# cabletester.net
KiCad netlist of a schematic drawn in EAGLE
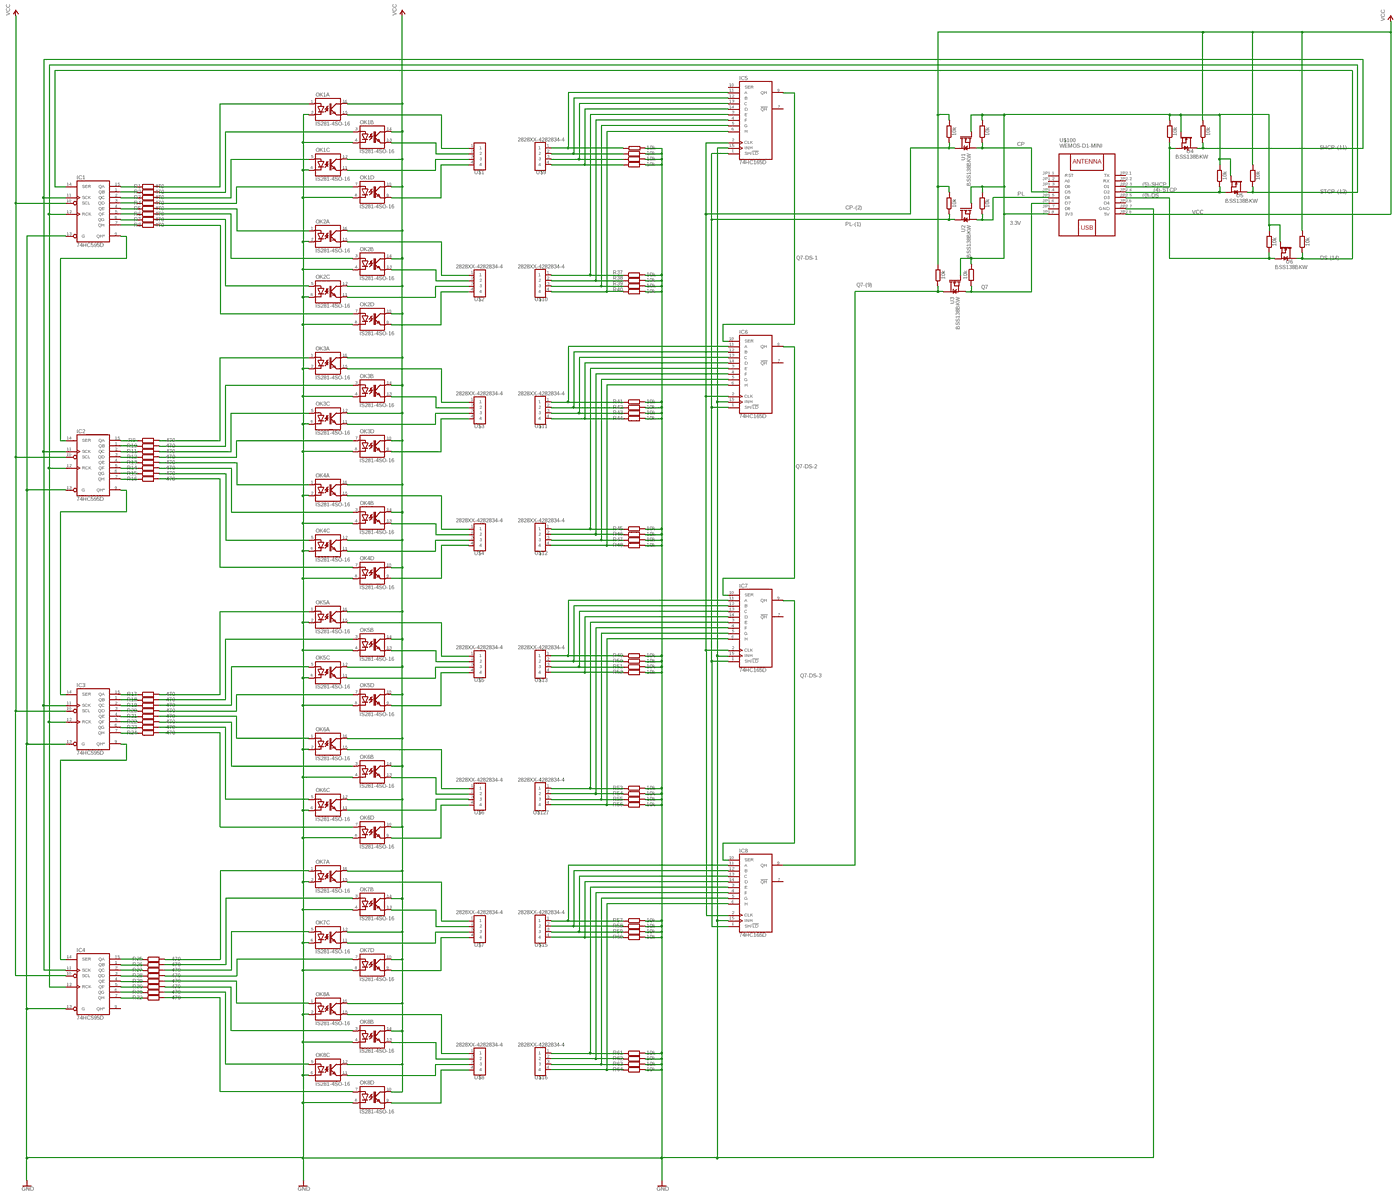
[diagram p0: schematic, sheet 1, overview]
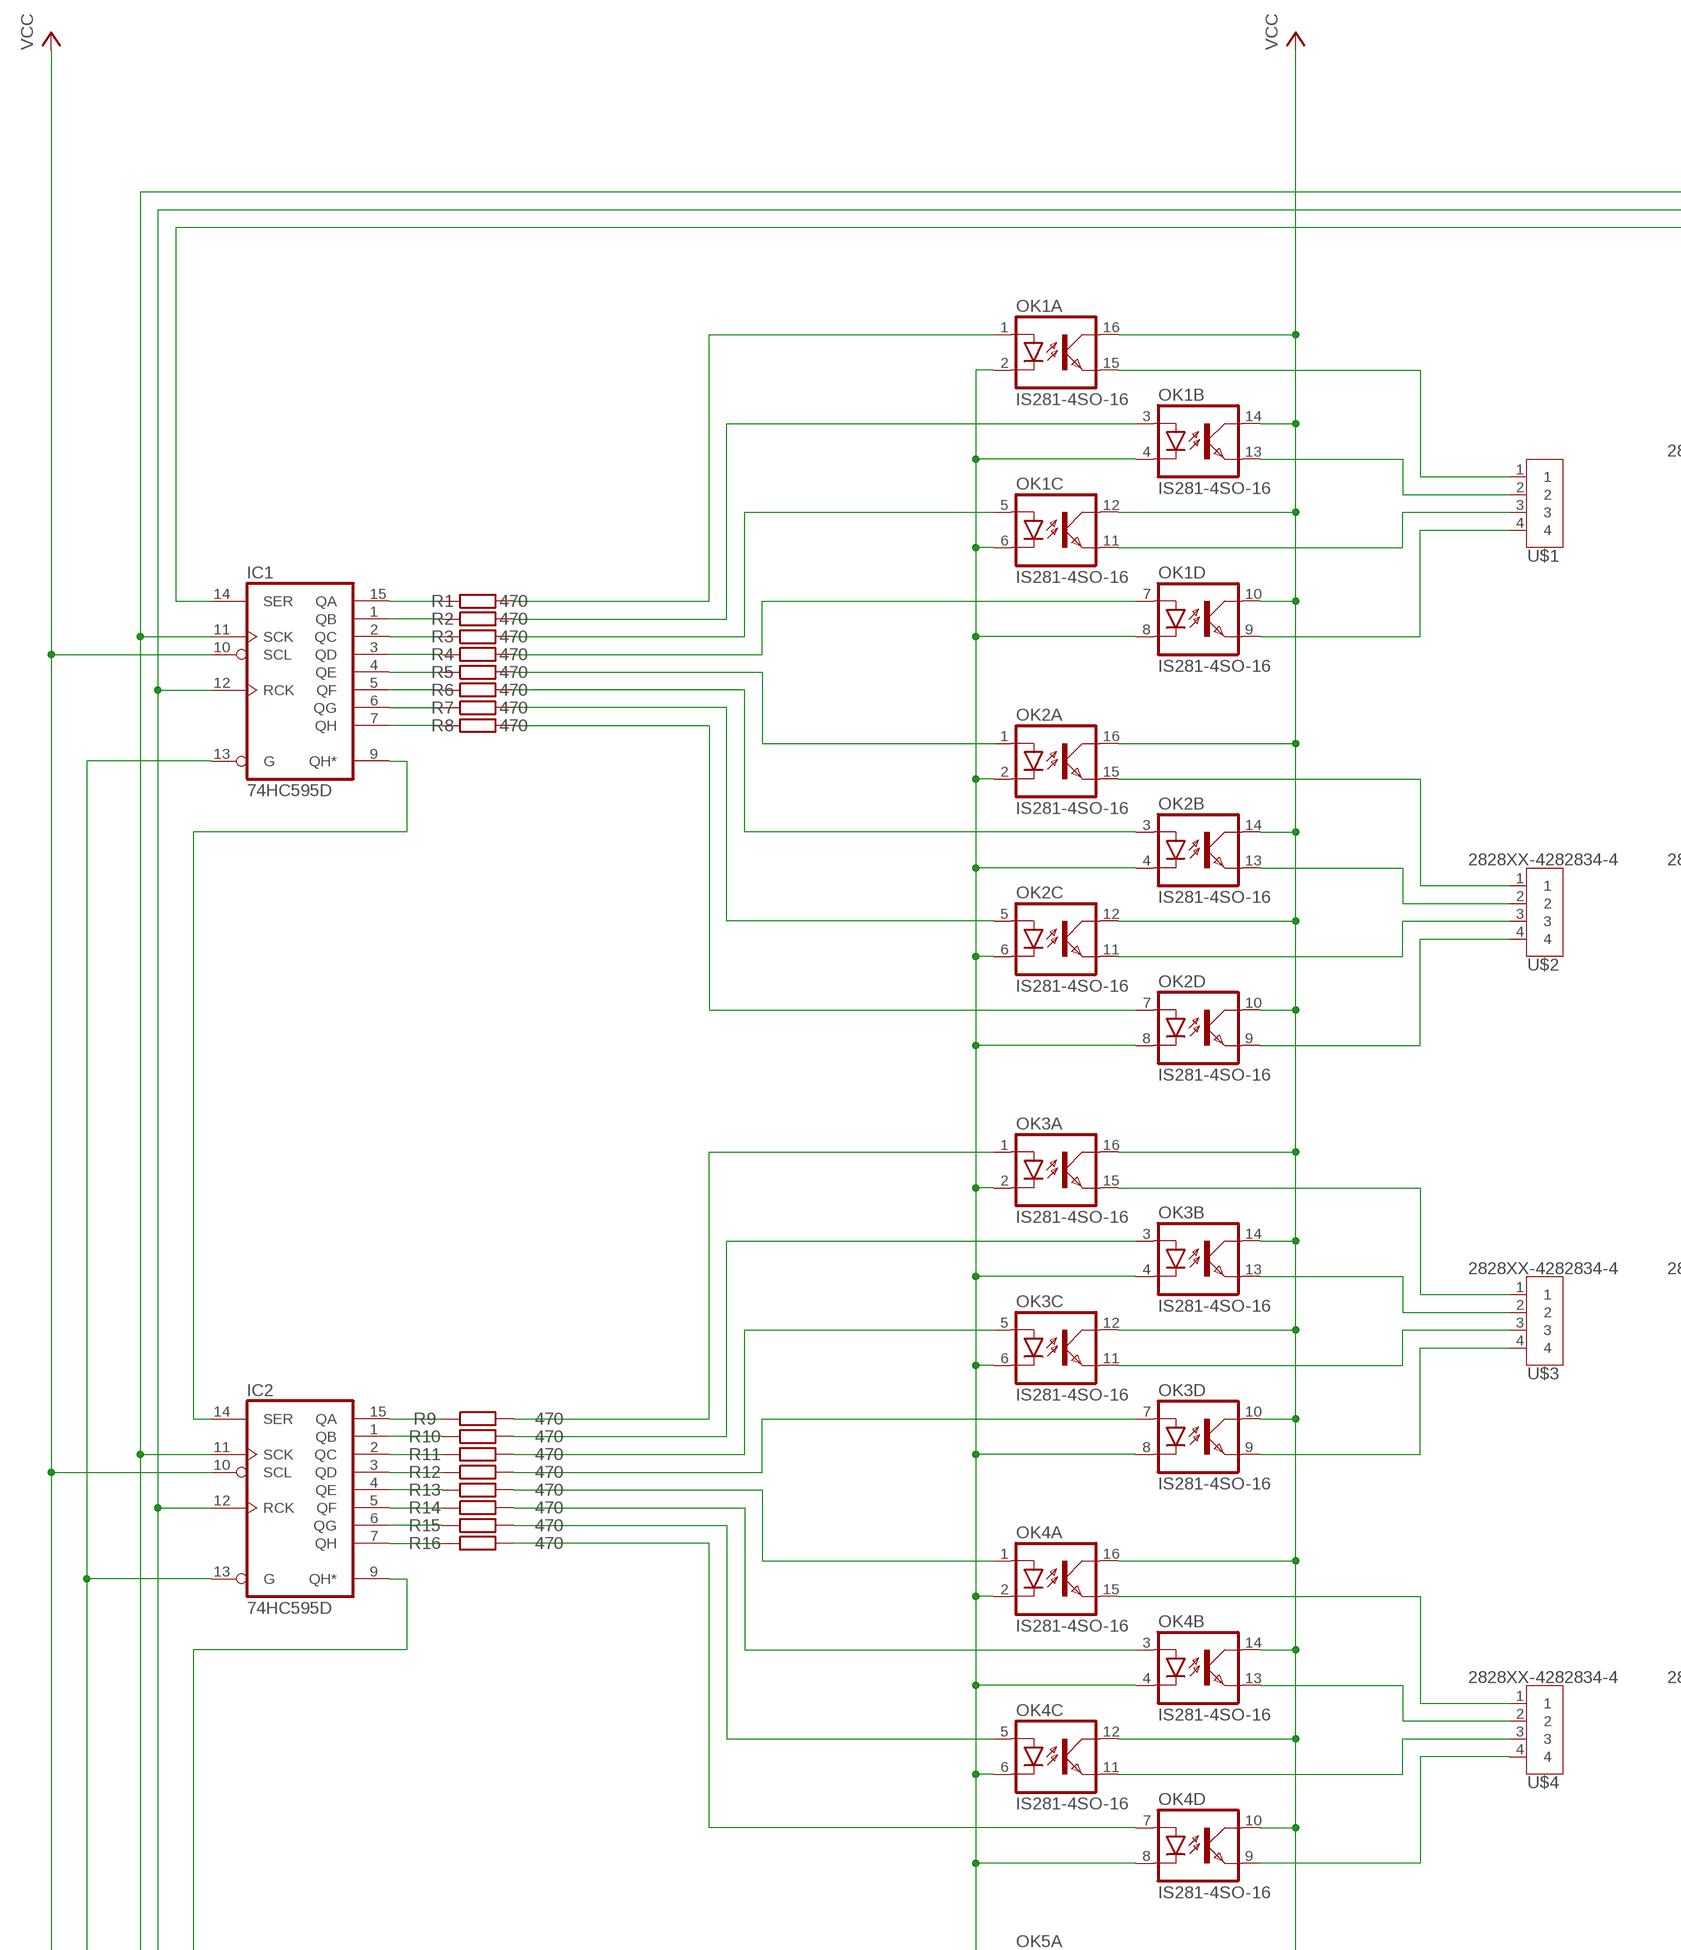
[diagram p1: schematic, sheet 1, part 1 of 4]
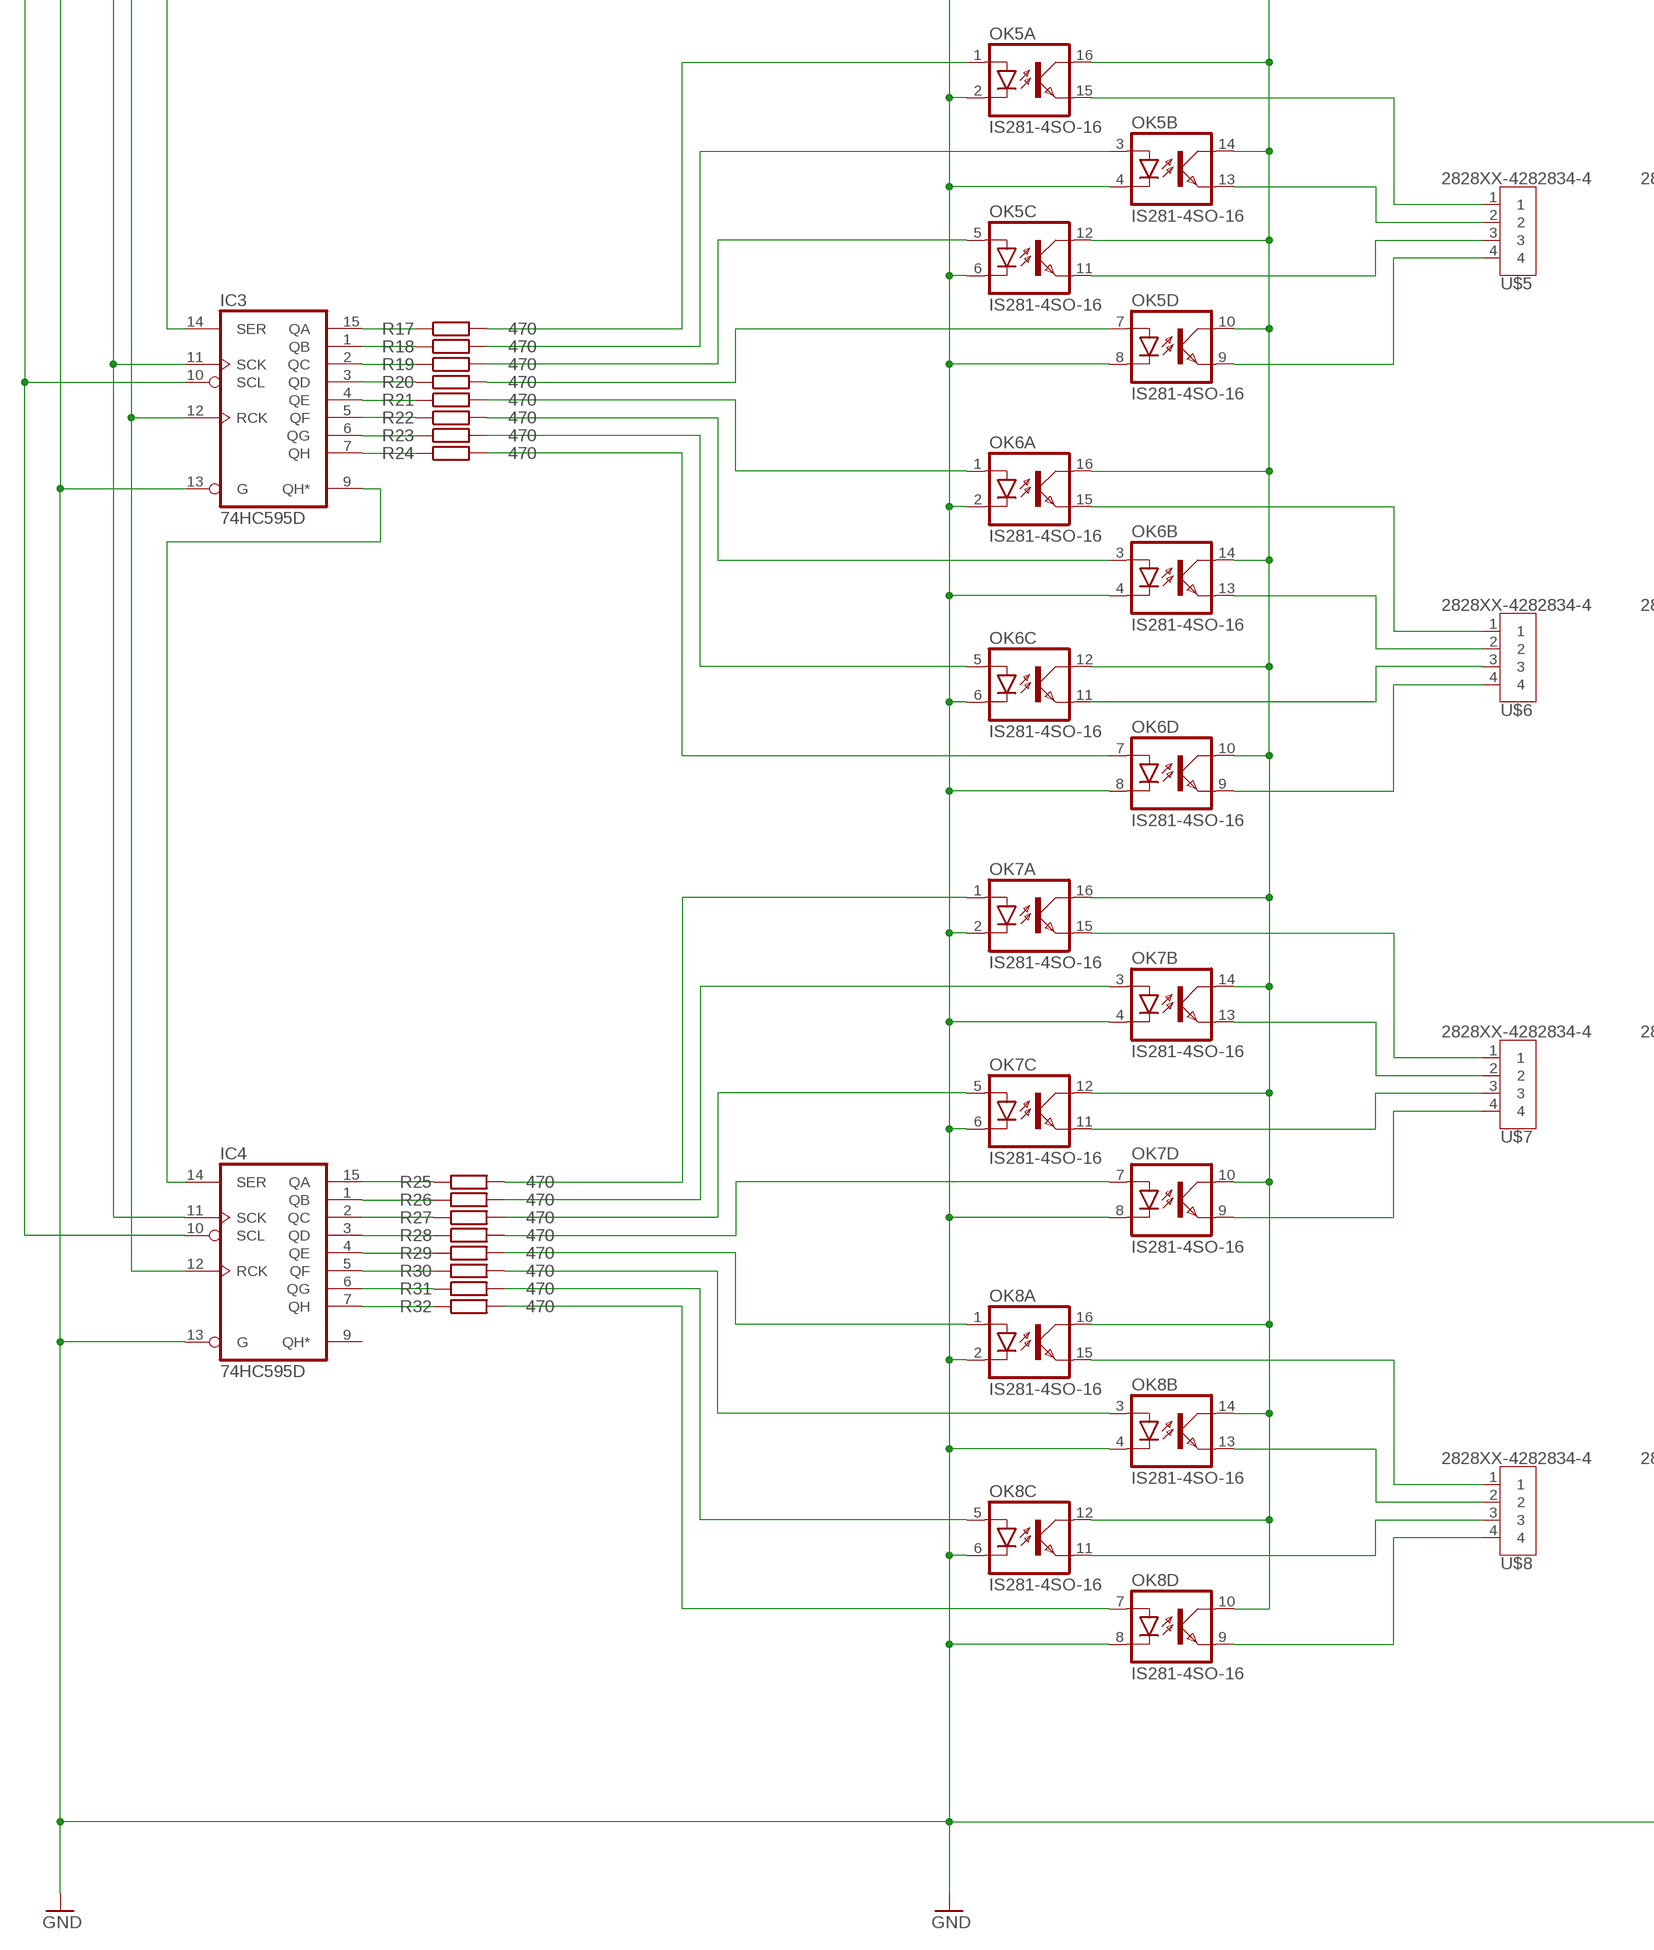
[diagram p2: schematic, sheet 1, part 2 of 4]
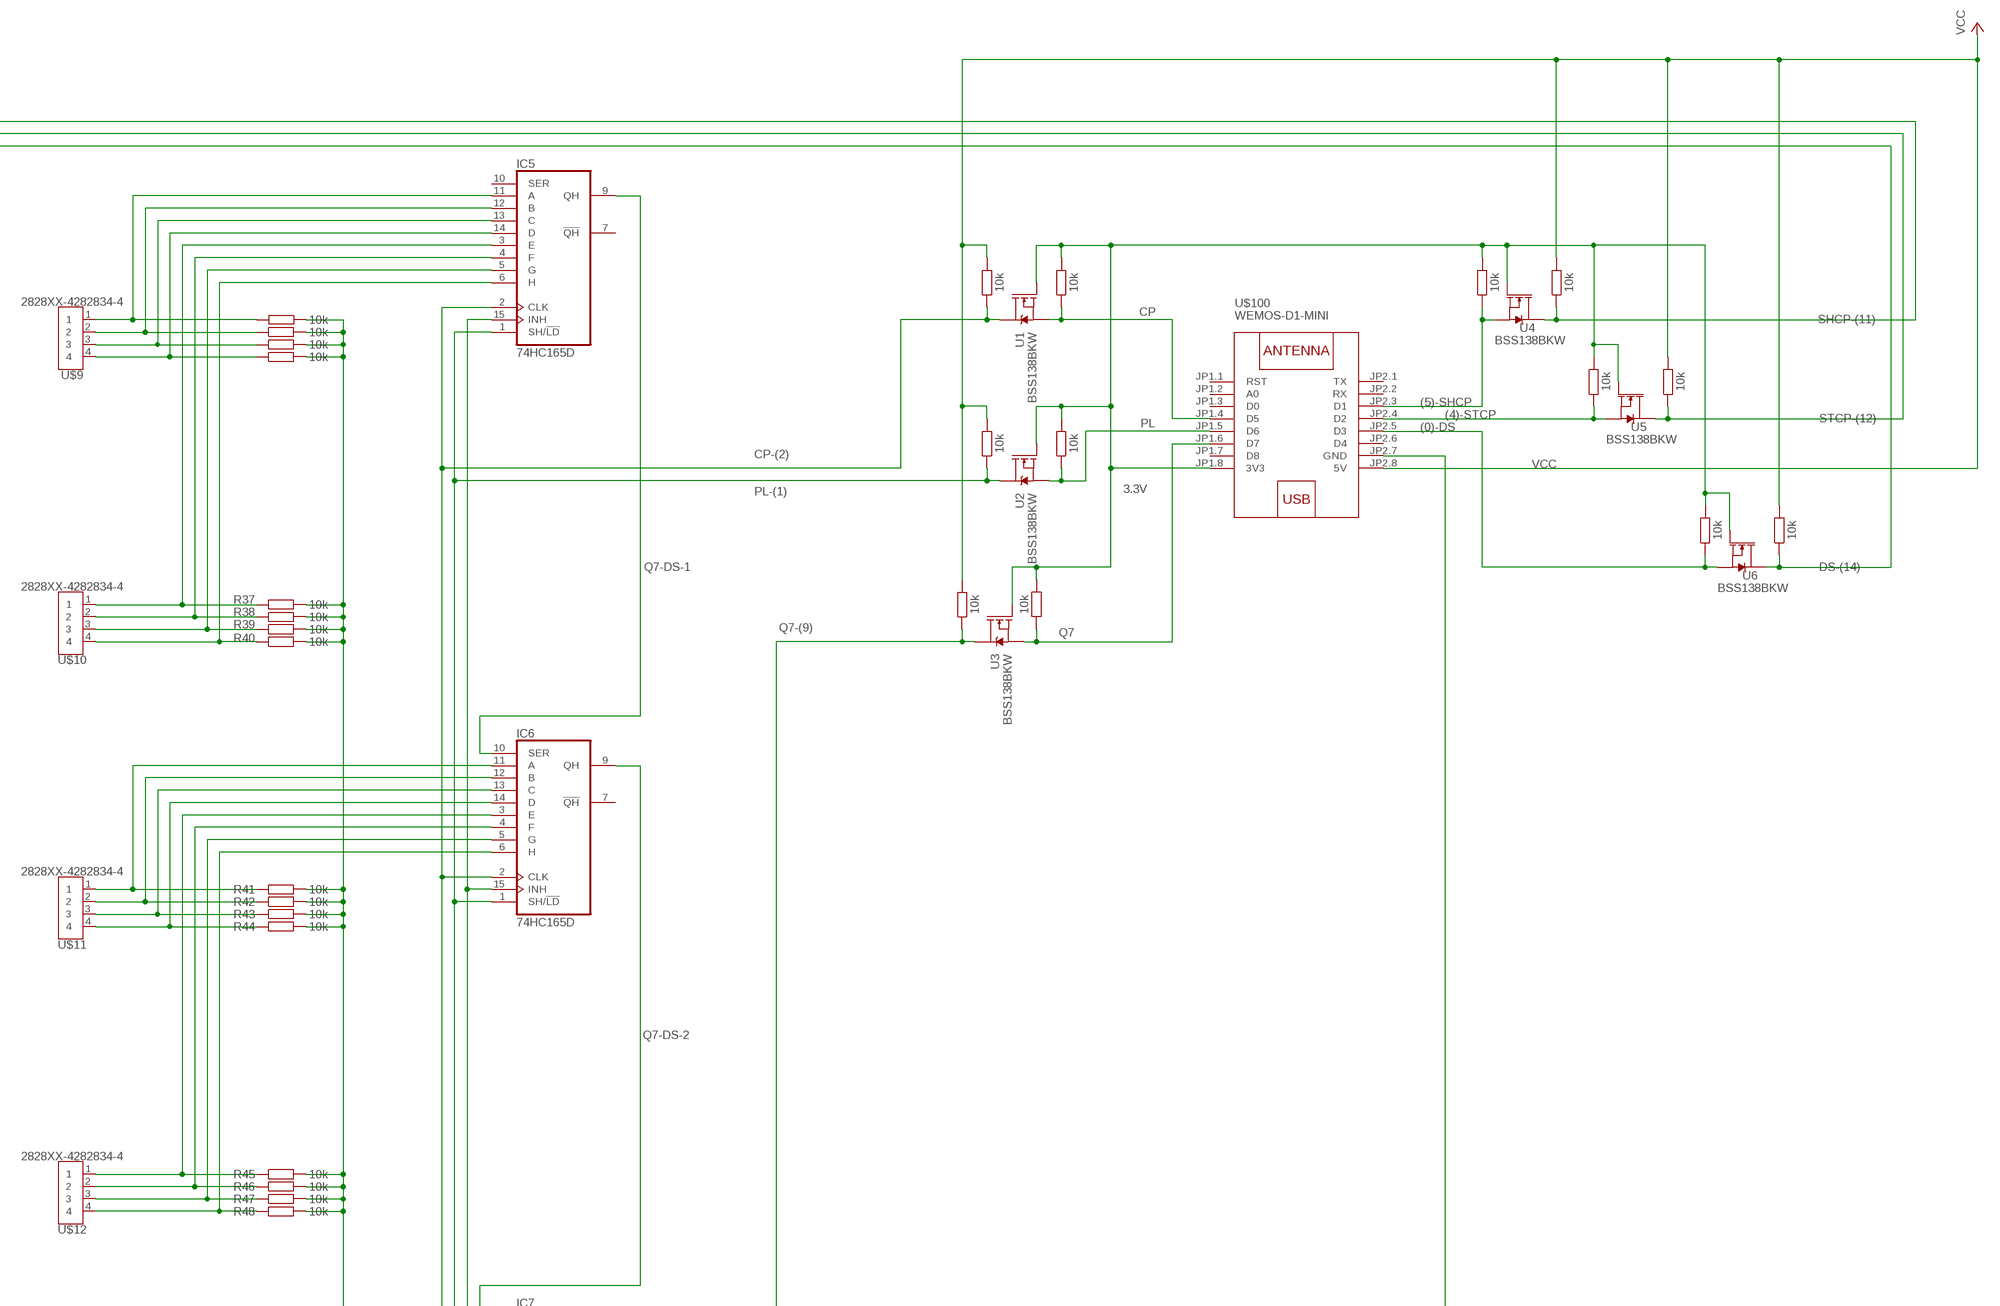
[diagram p3: schematic, sheet 1, part 3 of 4]
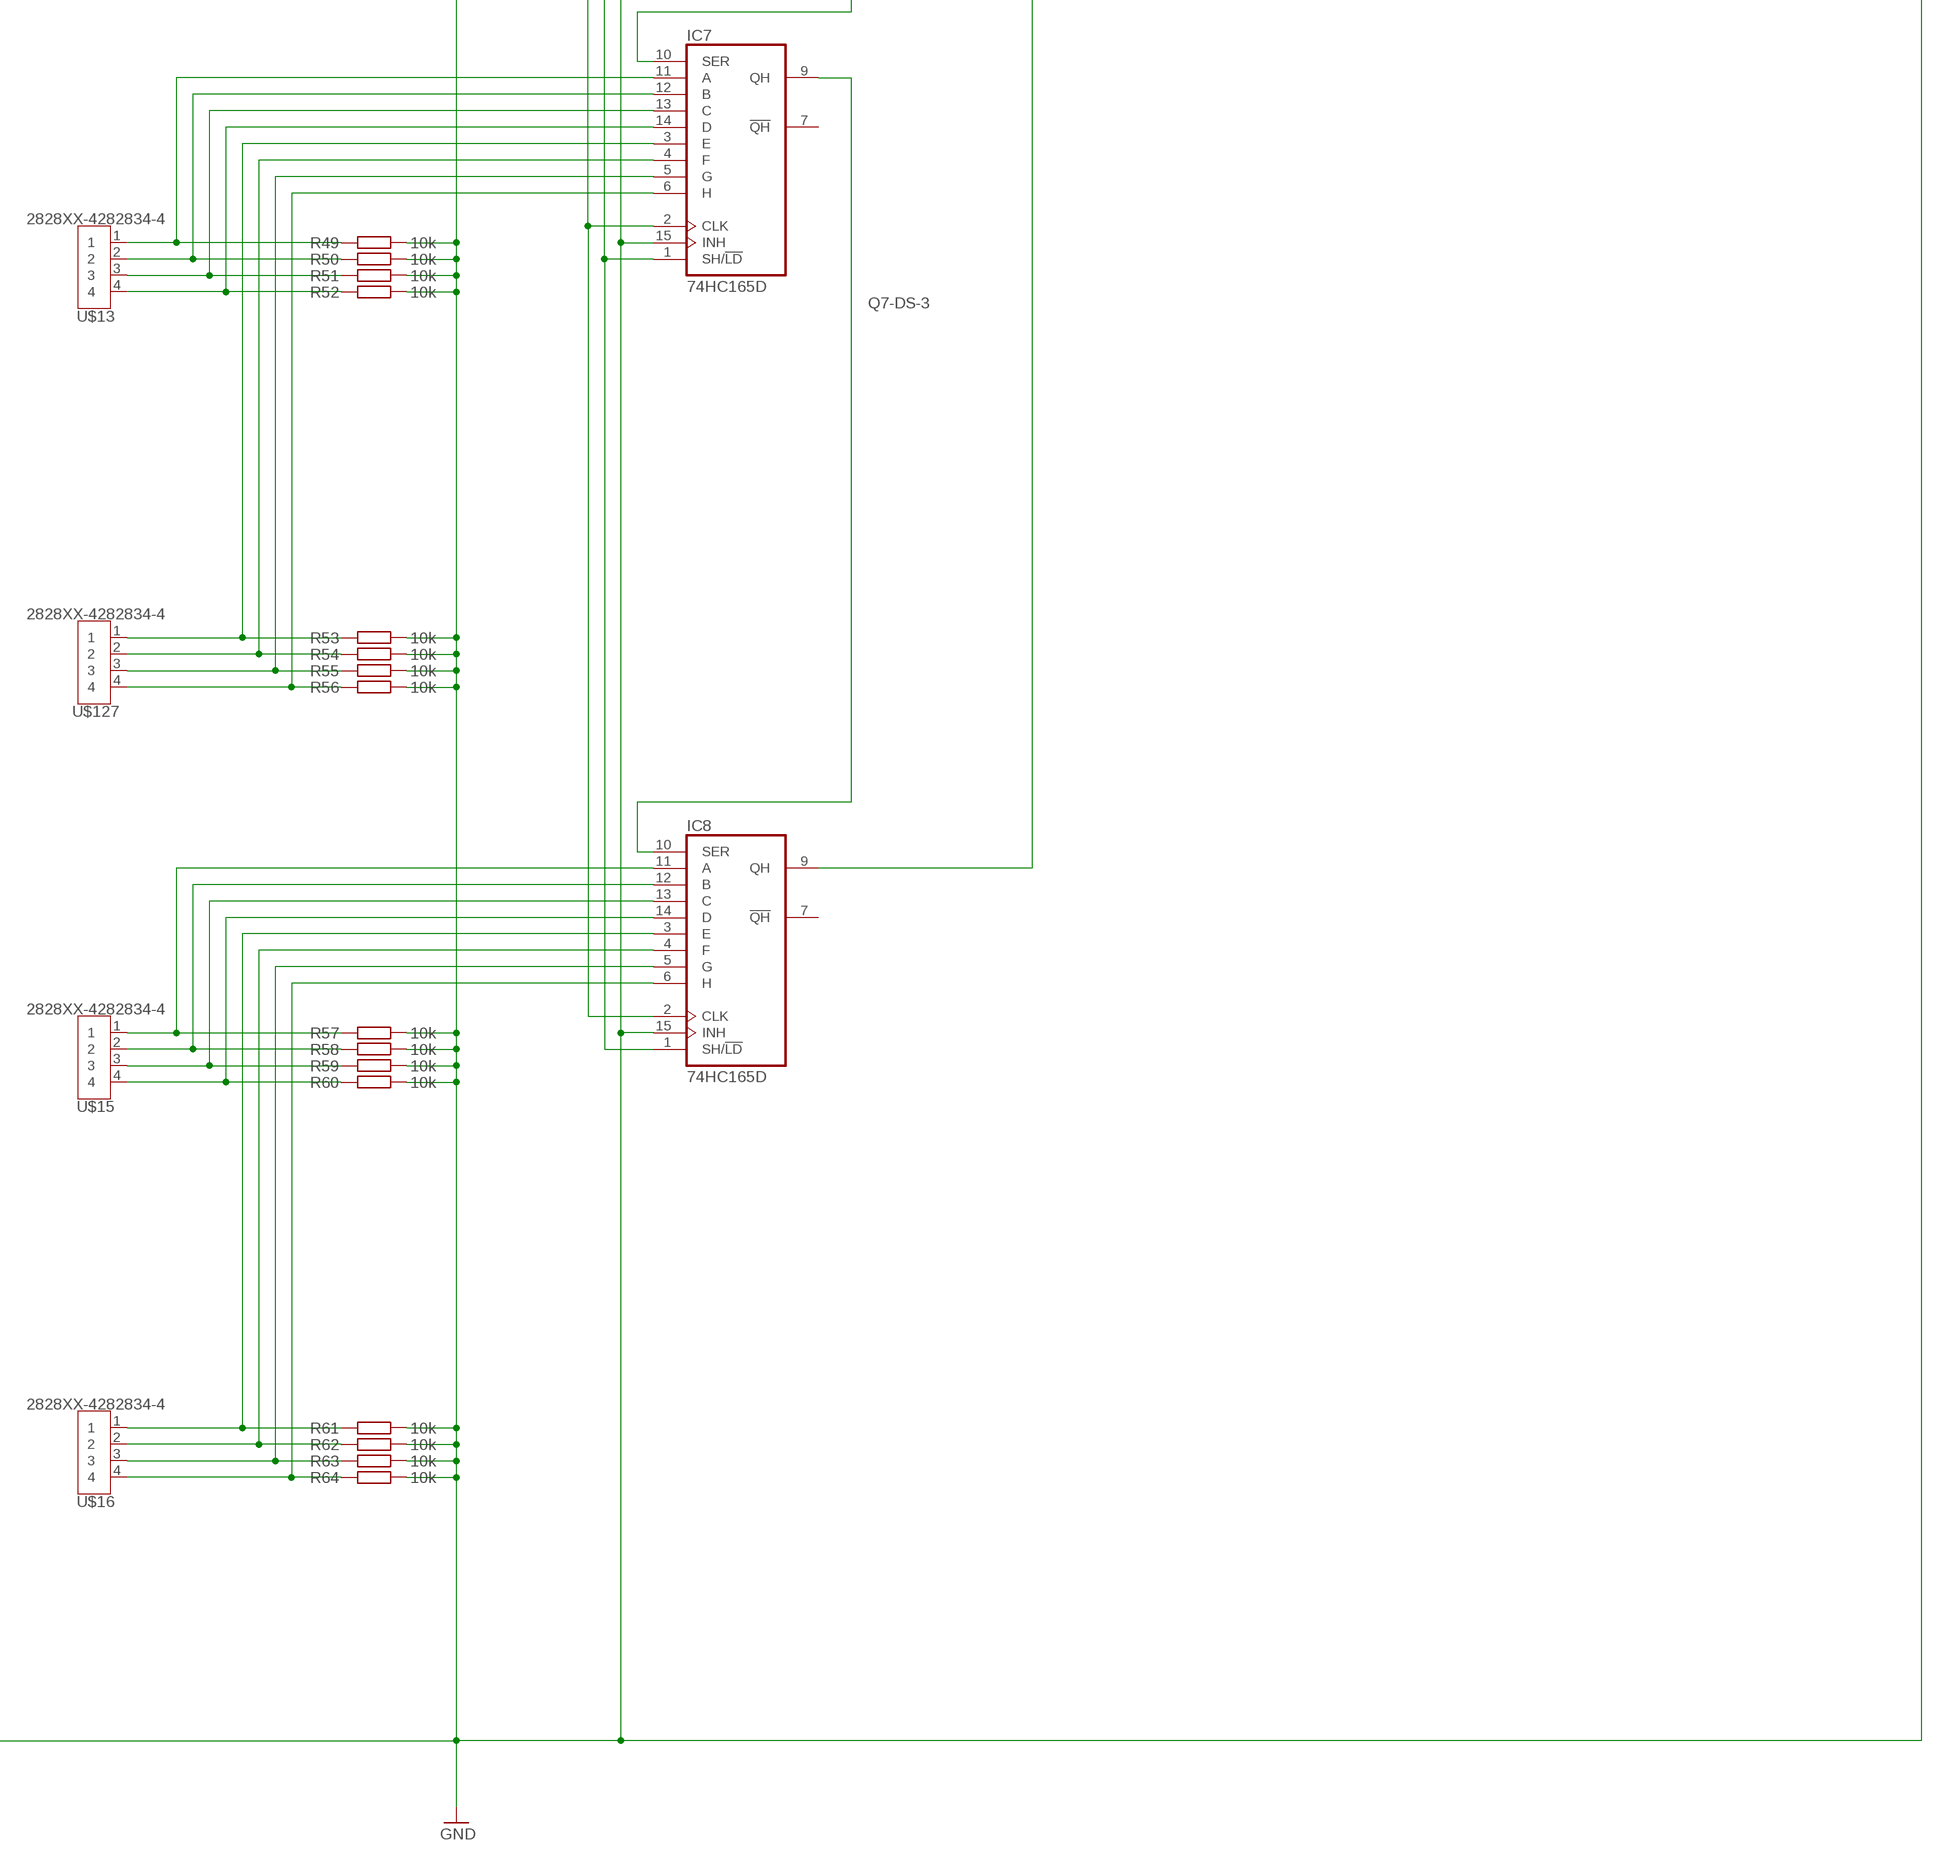
[diagram p4: schematic, sheet 1, part 4 of 4]

(export (version "E")
  (design (tool "Eeschema 10.0.6"))
  (components
    (comp (ref "IC1")
      (value "74HC595D")
      (footprint "eagle-import:SO16")
      (libsource (lib "eagle-import") (part "74595DHC"))
    )
    (comp (ref "IC2")
      (value "74HC595D")
      (footprint "eagle-import:SO16")
      (libsource (lib "eagle-import") (part "74595DHC"))
    )
    (comp (ref "IC3")
      (value "74HC595D")
      (footprint "eagle-import:SO16")
      (libsource (lib "eagle-import") (part "74595DHC"))
    )
    (comp (ref "IC4")
      (value "74HC595D")
      (footprint "eagle-import:SO16")
      (libsource (lib "eagle-import") (part "74595DHC"))
    )
    (comp (ref "IC5")
      (value "74HC165D")
      (footprint "eagle-import:SO16")
      (libsource (lib "eagle-import") (part "74165DHC"))
    )
    (comp (ref "IC6")
      (value "74HC165D")
      (footprint "eagle-import:SO16")
      (libsource (lib "eagle-import") (part "74165DHC"))
    )
    (comp (ref "IC7")
      (value "74HC165D")
      (footprint "eagle-import:SO16")
      (libsource (lib "eagle-import") (part "74165DHC"))
    )
    (comp (ref "IC8")
      (value "74HC165D")
      (footprint "eagle-import:SO16")
      (libsource (lib "eagle-import") (part "74165DHC"))
    )
    (comp (ref "OK1")
      (value "IS281-4SO-16")
      (footprint "eagle-import:SO16")
      (libsource (lib "eagle-import") (part "IS281-4SO-16"))
    )
    (comp (ref "OK2")
      (value "IS281-4SO-16")
      (footprint "eagle-import:SO16")
      (libsource (lib "eagle-import") (part "IS281-4SO-16"))
    )
    (comp (ref "OK3")
      (value "IS281-4SO-16")
      (footprint "eagle-import:SO16")
      (libsource (lib "eagle-import") (part "IS281-4SO-16"))
    )
    (comp (ref "OK4")
      (value "IS281-4SO-16")
      (footprint "eagle-import:SO16")
      (libsource (lib "eagle-import") (part "IS281-4SO-16"))
    )
    (comp (ref "OK5")
      (value "IS281-4SO-16")
      (footprint "eagle-import:SO16")
      (libsource (lib "eagle-import") (part "IS281-4SO-16"))
    )
    (comp (ref "OK6")
      (value "IS281-4SO-16")
      (footprint "eagle-import:SO16")
      (libsource (lib "eagle-import") (part "IS281-4SO-16"))
    )
    (comp (ref "OK7")
      (value "IS281-4SO-16")
      (footprint "eagle-import:SO16")
      (libsource (lib "eagle-import") (part "IS281-4SO-16"))
    )
    (comp (ref "OK8")
      (value "IS281-4SO-16")
      (footprint "eagle-import:SO16")
      (libsource (lib "eagle-import") (part "IS281-4SO-16"))
    )
    (comp (ref "R1")
      (value "470")
      (footprint "eagle-import:RESC3216X70")
      (libsource (lib "eagle-import") (part "RCHIP-1206(3216-METRIC)_"))
    )
    (comp (ref "R2")
      (value "470")
      (footprint "eagle-import:RESC3216X70")
      (libsource (lib "eagle-import") (part "RCHIP-1206(3216-METRIC)_"))
    )
    (comp (ref "R3")
      (value "470")
      (footprint "eagle-import:RESC3216X70")
      (libsource (lib "eagle-import") (part "RCHIP-1206(3216-METRIC)_"))
    )
    (comp (ref "R4")
      (value "470")
      (footprint "eagle-import:RESC3216X70")
      (libsource (lib "eagle-import") (part "RCHIP-1206(3216-METRIC)_"))
    )
    (comp (ref "R5")
      (value "470")
      (footprint "eagle-import:RESC3216X70")
      (libsource (lib "eagle-import") (part "RCHIP-1206(3216-METRIC)_"))
    )
    (comp (ref "R6")
      (value "470")
      (footprint "eagle-import:RESC3216X70")
      (libsource (lib "eagle-import") (part "RCHIP-1206(3216-METRIC)_"))
    )
    (comp (ref "R7")
      (value "470")
      (footprint "eagle-import:RESC3216X70")
      (libsource (lib "eagle-import") (part "RCHIP-1206(3216-METRIC)_"))
    )
    (comp (ref "R8")
      (value "470")
      (footprint "eagle-import:RESC3216X70")
      (libsource (lib "eagle-import") (part "RCHIP-1206(3216-METRIC)_"))
    )
    (comp (ref "R9")
      (value "470")
      (footprint "eagle-import:RESC3216X70")
      (libsource (lib "eagle-import") (part "RCHIP-1206(3216-METRIC)_"))
    )
    (comp (ref "R10")
      (value "470")
      (footprint "eagle-import:RESC3216X70")
      (libsource (lib "eagle-import") (part "RCHIP-1206(3216-METRIC)_"))
    )
    (comp (ref "R11")
      (value "470")
      (footprint "eagle-import:RESC3216X70")
      (libsource (lib "eagle-import") (part "RCHIP-1206(3216-METRIC)_"))
    )
    (comp (ref "R12")
      (value "470")
      (footprint "eagle-import:RESC3216X70")
      (libsource (lib "eagle-import") (part "RCHIP-1206(3216-METRIC)_"))
    )
    (comp (ref "R13")
      (value "470")
      (footprint "eagle-import:RESC3216X70")
      (libsource (lib "eagle-import") (part "RCHIP-1206(3216-METRIC)_"))
    )
    (comp (ref "R14")
      (value "470")
      (footprint "eagle-import:RESC3216X70")
      (libsource (lib "eagle-import") (part "RCHIP-1206(3216-METRIC)_"))
    )
    (comp (ref "R15")
      (value "470")
      (footprint "eagle-import:RESC3216X70")
      (libsource (lib "eagle-import") (part "RCHIP-1206(3216-METRIC)_"))
    )
    (comp (ref "R16")
      (value "470")
      (footprint "eagle-import:RESC3216X70")
      (libsource (lib "eagle-import") (part "RCHIP-1206(3216-METRIC)_"))
    )
    (comp (ref "R17")
      (value "470")
      (footprint "eagle-import:RESC3216X70")
      (libsource (lib "eagle-import") (part "RCHIP-1206(3216-METRIC)_"))
    )
    (comp (ref "R18")
      (value "470")
      (footprint "eagle-import:RESC3216X70")
      (libsource (lib "eagle-import") (part "RCHIP-1206(3216-METRIC)_"))
    )
    (comp (ref "R19")
      (value "470")
      (footprint "eagle-import:RESC3216X70")
      (libsource (lib "eagle-import") (part "RCHIP-1206(3216-METRIC)_"))
    )
    (comp (ref "R20")
      (value "470")
      (footprint "eagle-import:RESC3216X70")
      (libsource (lib "eagle-import") (part "RCHIP-1206(3216-METRIC)_"))
    )
    (comp (ref "R21")
      (value "470")
      (footprint "eagle-import:RESC3216X70")
      (libsource (lib "eagle-import") (part "RCHIP-1206(3216-METRIC)_"))
    )
    (comp (ref "R22")
      (value "470")
      (footprint "eagle-import:RESC3216X70")
      (libsource (lib "eagle-import") (part "RCHIP-1206(3216-METRIC)_"))
    )
    (comp (ref "R23")
      (value "470")
      (footprint "eagle-import:RESC3216X70")
      (libsource (lib "eagle-import") (part "RCHIP-1206(3216-METRIC)_"))
    )
    (comp (ref "R24")
      (value "470")
      (footprint "eagle-import:RESC3216X70")
      (libsource (lib "eagle-import") (part "RCHIP-1206(3216-METRIC)_"))
    )
    (comp (ref "R25")
      (value "470")
      (footprint "eagle-import:RESC3216X70")
      (libsource (lib "eagle-import") (part "RCHIP-1206(3216-METRIC)_"))
    )
    (comp (ref "R26")
      (value "470")
      (footprint "eagle-import:RESC3216X70")
      (libsource (lib "eagle-import") (part "RCHIP-1206(3216-METRIC)_"))
    )
    (comp (ref "R27")
      (value "470")
      (footprint "eagle-import:RESC3216X70")
      (libsource (lib "eagle-import") (part "RCHIP-1206(3216-METRIC)_"))
    )
    (comp (ref "R28")
      (value "470")
      (footprint "eagle-import:RESC3216X70")
      (libsource (lib "eagle-import") (part "RCHIP-1206(3216-METRIC)_"))
    )
    (comp (ref "R29")
      (value "470")
      (footprint "eagle-import:RESC3216X70")
      (libsource (lib "eagle-import") (part "RCHIP-1206(3216-METRIC)_"))
    )
    (comp (ref "R30")
      (value "470")
      (footprint "eagle-import:RESC3216X70")
      (libsource (lib "eagle-import") (part "RCHIP-1206(3216-METRIC)_"))
    )
    (comp (ref "R31")
      (value "470")
      (footprint "eagle-import:RESC3216X70")
      (libsource (lib "eagle-import") (part "RCHIP-1206(3216-METRIC)_"))
    )
    (comp (ref "R32")
      (value "470")
      (footprint "eagle-import:RESC3216X70")
      (libsource (lib "eagle-import") (part "RCHIP-1206(3216-METRIC)_"))
    )
    (comp (ref "R33")
      (value "10k")
      (footprint "eagle-import:RESC3216X70")
      (libsource (lib "eagle-import") (part "RCHIP-1206(3216-METRIC)_"))
    )
    (comp (ref "R34")
      (value "10k")
      (footprint "eagle-import:RESC3216X70")
      (libsource (lib "eagle-import") (part "RCHIP-1206(3216-METRIC)_"))
    )
    (comp (ref "R35")
      (value "10k")
      (footprint "eagle-import:RESC3216X70")
      (libsource (lib "eagle-import") (part "RCHIP-1206(3216-METRIC)_"))
    )
    (comp (ref "R36")
      (value "10k")
      (footprint "eagle-import:RESC3216X70")
      (libsource (lib "eagle-import") (part "RCHIP-1206(3216-METRIC)_"))
    )
    (comp (ref "R37")
      (value "10k")
      (footprint "eagle-import:RESC3216X70")
      (libsource (lib "eagle-import") (part "RCHIP-1206(3216-METRIC)_"))
    )
    (comp (ref "R38")
      (value "10k")
      (footprint "eagle-import:RESC3216X70")
      (libsource (lib "eagle-import") (part "RCHIP-1206(3216-METRIC)_"))
    )
    (comp (ref "R39")
      (value "10k")
      (footprint "eagle-import:RESC3216X70")
      (libsource (lib "eagle-import") (part "RCHIP-1206(3216-METRIC)_"))
    )
    (comp (ref "R40")
      (value "10k")
      (footprint "eagle-import:RESC3216X70")
      (libsource (lib "eagle-import") (part "RCHIP-1206(3216-METRIC)_"))
    )
    (comp (ref "R41")
      (value "10k")
      (footprint "eagle-import:RESC3216X70")
      (libsource (lib "eagle-import") (part "RCHIP-1206(3216-METRIC)_"))
    )
    (comp (ref "R42")
      (value "10k")
      (footprint "eagle-import:RESC3216X70")
      (libsource (lib "eagle-import") (part "RCHIP-1206(3216-METRIC)_"))
    )
    (comp (ref "R43")
      (value "10k")
      (footprint "eagle-import:RESC3216X70")
      (libsource (lib "eagle-import") (part "RCHIP-1206(3216-METRIC)_"))
    )
    (comp (ref "R44")
      (value "10k")
      (footprint "eagle-import:RESC3216X70")
      (libsource (lib "eagle-import") (part "RCHIP-1206(3216-METRIC)_"))
    )
    (comp (ref "R45")
      (value "10k")
      (footprint "eagle-import:RESC3216X70")
      (libsource (lib "eagle-import") (part "RCHIP-1206(3216-METRIC)_"))
    )
    (comp (ref "R46")
      (value "10k")
      (footprint "eagle-import:RESC3216X70")
      (libsource (lib "eagle-import") (part "RCHIP-1206(3216-METRIC)_"))
    )
    (comp (ref "R47")
      (value "10k")
      (footprint "eagle-import:RESC3216X70")
      (libsource (lib "eagle-import") (part "RCHIP-1206(3216-METRIC)_"))
    )
    (comp (ref "R48")
      (value "10k")
      (footprint "eagle-import:RESC3216X70")
      (libsource (lib "eagle-import") (part "RCHIP-1206(3216-METRIC)_"))
    )
    (comp (ref "R49")
      (value "10k")
      (footprint "eagle-import:RESC3216X70")
      (libsource (lib "eagle-import") (part "RCHIP-1206(3216-METRIC)_"))
    )
    (comp (ref "R50")
      (value "10k")
      (footprint "eagle-import:RESC3216X70")
      (libsource (lib "eagle-import") (part "RCHIP-1206(3216-METRIC)_"))
    )
    (comp (ref "R51")
      (value "10k")
      (footprint "eagle-import:RESC3216X70")
      (libsource (lib "eagle-import") (part "RCHIP-1206(3216-METRIC)_"))
    )
    (comp (ref "R52")
      (value "10k")
      (footprint "eagle-import:RESC3216X70")
      (libsource (lib "eagle-import") (part "RCHIP-1206(3216-METRIC)_"))
    )
    (comp (ref "R53")
      (value "10k")
      (footprint "eagle-import:RESC3216X70")
      (libsource (lib "eagle-import") (part "RCHIP-1206(3216-METRIC)_"))
    )
    (comp (ref "R54")
      (value "10k")
      (footprint "eagle-import:RESC3216X70")
      (libsource (lib "eagle-import") (part "RCHIP-1206(3216-METRIC)_"))
    )
    (comp (ref "R55")
      (value "10k")
      (footprint "eagle-import:RESC3216X70")
      (libsource (lib "eagle-import") (part "RCHIP-1206(3216-METRIC)_"))
    )
    (comp (ref "R56")
      (value "10k")
      (footprint "eagle-import:RESC3216X70")
      (libsource (lib "eagle-import") (part "RCHIP-1206(3216-METRIC)_"))
    )
    (comp (ref "R57")
      (value "10k")
      (footprint "eagle-import:RESC3216X70")
      (libsource (lib "eagle-import") (part "RCHIP-1206(3216-METRIC)_"))
    )
    (comp (ref "R58")
      (value "10k")
      (footprint "eagle-import:RESC3216X70")
      (libsource (lib "eagle-import") (part "RCHIP-1206(3216-METRIC)_"))
    )
    (comp (ref "R59")
      (value "10k")
      (footprint "eagle-import:RESC3216X70")
      (libsource (lib "eagle-import") (part "RCHIP-1206(3216-METRIC)_"))
    )
    (comp (ref "R60")
      (value "10k")
      (footprint "eagle-import:RESC3216X70")
      (libsource (lib "eagle-import") (part "RCHIP-1206(3216-METRIC)_"))
    )
    (comp (ref "R61")
      (value "10k")
      (footprint "eagle-import:RESC3216X70")
      (libsource (lib "eagle-import") (part "RCHIP-1206(3216-METRIC)_"))
    )
    (comp (ref "R62")
      (value "10k")
      (footprint "eagle-import:RESC3216X70")
      (libsource (lib "eagle-import") (part "RCHIP-1206(3216-METRIC)_"))
    )
    (comp (ref "R63")
      (value "10k")
      (footprint "eagle-import:RESC3216X70")
      (libsource (lib "eagle-import") (part "RCHIP-1206(3216-METRIC)_"))
    )
    (comp (ref "R64")
      (value "10k")
      (footprint "eagle-import:RESC3216X70")
      (libsource (lib "eagle-import") (part "RCHIP-1206(3216-METRIC)_"))
    )
    (comp (ref "R65")
      (value "10k")
      (footprint "eagle-import:RESC3216X70")
      (libsource (lib "eagle-import") (part "RCHIP-1206(3216-METRIC)_"))
    )
    (comp (ref "R66")
      (value "10k")
      (footprint "eagle-import:RESC3216X70")
      (libsource (lib "eagle-import") (part "RCHIP-1206(3216-METRIC)_"))
    )
    (comp (ref "R67")
      (value "10k")
      (footprint "eagle-import:RESC3216X70")
      (libsource (lib "eagle-import") (part "RCHIP-1206(3216-METRIC)_"))
    )
    (comp (ref "R68")
      (value "10k")
      (footprint "eagle-import:RESC3216X70")
      (libsource (lib "eagle-import") (part "RCHIP-1206(3216-METRIC)_"))
    )
    (comp (ref "R69")
      (value "10k")
      (footprint "eagle-import:RESC3216X70")
      (libsource (lib "eagle-import") (part "RCHIP-1206(3216-METRIC)_"))
    )
    (comp (ref "R70")
      (value "10k")
      (footprint "eagle-import:RESC3216X70")
      (libsource (lib "eagle-import") (part "RCHIP-1206(3216-METRIC)_"))
    )
    (comp (ref "R71")
      (value "10k")
      (footprint "eagle-import:RESC3216X70")
      (libsource (lib "eagle-import") (part "RCHIP-1206(3216-METRIC)_"))
    )
    (comp (ref "R72")
      (value "10k")
      (footprint "eagle-import:RESC3216X70")
      (libsource (lib "eagle-import") (part "RCHIP-1206(3216-METRIC)_"))
    )
    (comp (ref "R73")
      (value "10k")
      (footprint "eagle-import:RESC3216X70")
      (libsource (lib "eagle-import") (part "RCHIP-1206(3216-METRIC)_"))
    )
    (comp (ref "R74")
      (value "10k")
      (footprint "eagle-import:RESC3216X70")
      (libsource (lib "eagle-import") (part "RCHIP-1206(3216-METRIC)_"))
    )
    (comp (ref "R75")
      (value "10k")
      (footprint "eagle-import:RESC3216X70")
      (libsource (lib "eagle-import") (part "RCHIP-1206(3216-METRIC)_"))
    )
    (comp (ref "R76")
      (value "10k")
      (footprint "eagle-import:RESC3216X70")
      (libsource (lib "eagle-import") (part "RCHIP-1206(3216-METRIC)_"))
    )
    (comp (ref "U$1")
      (value "2828XX-4282834-4")
      (footprint "eagle-import:TERMBLK_254-4N")
      (fields (field (name "MANUFACTURER") "TE Connectivity") (field (name "MPN") "282834-4"))
      (libsource (lib "eagle-import") (part "2828XX-4282834-4"))
    )
    (comp (ref "U$2")
      (value "2828XX-4282834-4")
      (footprint "eagle-import:TERMBLK_254-4N")
      (fields (field (name "MANUFACTURER") "TE Connectivity") (field (name "MPN") "282834-4"))
      (libsource (lib "eagle-import") (part "2828XX-4282834-4"))
    )
    (comp (ref "U$3")
      (value "2828XX-4282834-4")
      (footprint "eagle-import:TERMBLK_254-4N")
      (fields (field (name "MANUFACTURER") "TE Connectivity") (field (name "MPN") "282834-4"))
      (libsource (lib "eagle-import") (part "2828XX-4282834-4"))
    )
    (comp (ref "U$4")
      (value "2828XX-4282834-4")
      (footprint "eagle-import:TERMBLK_254-4N")
      (fields (field (name "MANUFACTURER") "TE Connectivity") (field (name "MPN") "282834-4"))
      (libsource (lib "eagle-import") (part "2828XX-4282834-4"))
    )
    (comp (ref "U$5")
      (value "2828XX-4282834-4")
      (footprint "eagle-import:TERMBLK_254-4N")
      (fields (field (name "MANUFACTURER") "TE Connectivity") (field (name "MPN") "282834-4"))
      (libsource (lib "eagle-import") (part "2828XX-4282834-4"))
    )
    (comp (ref "U$6")
      (value "2828XX-4282834-4")
      (footprint "eagle-import:TERMBLK_254-4N")
      (fields (field (name "MANUFACTURER") "TE Connectivity") (field (name "MPN") "282834-4"))
      (libsource (lib "eagle-import") (part "2828XX-4282834-4"))
    )
    (comp (ref "U$7")
      (value "2828XX-4282834-4")
      (footprint "eagle-import:TERMBLK_254-4N")
      (fields (field (name "MANUFACTURER") "TE Connectivity") (field (name "MPN") "282834-4"))
      (libsource (lib "eagle-import") (part "2828XX-4282834-4"))
    )
    (comp (ref "U$8")
      (value "2828XX-4282834-4")
      (footprint "eagle-import:TERMBLK_254-4N")
      (fields (field (name "MANUFACTURER") "TE Connectivity") (field (name "MPN") "282834-4"))
      (libsource (lib "eagle-import") (part "2828XX-4282834-4"))
    )
    (comp (ref "U$9")
      (value "2828XX-4282834-4")
      (footprint "eagle-import:TERMBLK_254-4N")
      (fields (field (name "MANUFACTURER") "TE Connectivity") (field (name "MPN") "282834-4"))
      (libsource (lib "eagle-import") (part "2828XX-4282834-4"))
    )
    (comp (ref "U$10")
      (value "2828XX-4282834-4")
      (footprint "eagle-import:TERMBLK_254-4N")
      (fields (field (name "MANUFACTURER") "TE Connectivity") (field (name "MPN") "282834-4"))
      (libsource (lib "eagle-import") (part "2828XX-4282834-4"))
    )
    (comp (ref "U$11")
      (value "2828XX-4282834-4")
      (footprint "eagle-import:TERMBLK_254-4N")
      (fields (field (name "MANUFACTURER") "TE Connectivity") (field (name "MPN") "282834-4"))
      (libsource (lib "eagle-import") (part "2828XX-4282834-4"))
    )
    (comp (ref "U$12")
      (value "2828XX-4282834-4")
      (footprint "eagle-import:TERMBLK_254-4N")
      (fields (field (name "MANUFACTURER") "TE Connectivity") (field (name "MPN") "282834-4"))
      (libsource (lib "eagle-import") (part "2828XX-4282834-4"))
    )
    (comp (ref "U$13")
      (value "2828XX-4282834-4")
      (footprint "eagle-import:TERMBLK_254-4N")
      (fields (field (name "MANUFACTURER") "TE Connectivity") (field (name "MPN") "282834-4"))
      (libsource (lib "eagle-import") (part "2828XX-4282834-4"))
    )
    (comp (ref "U$15")
      (value "2828XX-4282834-4")
      (footprint "eagle-import:TERMBLK_254-4N")
      (fields (field (name "MANUFACTURER") "TE Connectivity") (field (name "MPN") "282834-4"))
      (libsource (lib "eagle-import") (part "2828XX-4282834-4"))
    )
    (comp (ref "U$16")
      (value "2828XX-4282834-4")
      (footprint "eagle-import:TERMBLK_254-4N")
      (fields (field (name "MANUFACTURER") "TE Connectivity") (field (name "MPN") "282834-4"))
      (libsource (lib "eagle-import") (part "2828XX-4282834-4"))
    )
    (comp (ref "U$100")
      (value "WEMOS-D1-MINI")
      (footprint "eagle-import:WEMOS-D1-MINI")
      (libsource (lib "eagle-import") (part "WEMOS-D1-MINI"))
    )
    (comp (ref "U$127")
      (value "2828XX-4282834-4")
      (footprint "eagle-import:TERMBLK_254-4N")
      (fields (field (name "MANUFACTURER") "TE Connectivity") (field (name "MPN") "282834-4"))
      (libsource (lib "eagle-import") (part "2828XX-4282834-4"))
    )
    (comp (ref "U1")
      (value "BSS138BKW")
      (footprint "eagle-import:SOT65P210X110-3N")
      (libsource (lib "eagle-import") (part "BSS138BKW"))
    )
    (comp (ref "U2")
      (value "BSS138BKW")
      (footprint "eagle-import:SOT65P210X110-3N")
      (libsource (lib "eagle-import") (part "BSS138BKW"))
    )
    (comp (ref "U3")
      (value "BSS138BKW")
      (footprint "eagle-import:SOT65P210X110-3N")
      (libsource (lib "eagle-import") (part "BSS138BKW"))
    )
    (comp (ref "U4")
      (value "BSS138BKW")
      (footprint "eagle-import:SOT65P210X110-3N")
      (libsource (lib "eagle-import") (part "BSS138BKW"))
    )
    (comp (ref "U5")
      (value "BSS138BKW")
      (footprint "eagle-import:SOT65P210X110-3N")
      (libsource (lib "eagle-import") (part "BSS138BKW"))
    )
    (comp (ref "U6")
      (value "BSS138BKW")
      (footprint "eagle-import:SOT65P210X110-3N")
      (libsource (lib "eagle-import") (part "BSS138BKW"))
    )
  )
  (nets
    (net (code "1") (name "/(0)-DS") (class "Default")
      (node (ref "R75") (pin "1") (pinfunction "1_1") (pintype "passive"))
      (node (ref "U$100") (pin "JP2.5") (pinfunction "D3_JP2.5") (pintype "bidirectional"))
      (node (ref "U6") (pin "2") (pinfunction "S_2") (pintype "bidirectional"))
    )
    (net (code "2") (name "/(4)-STCP") (class "Default")
      (node (ref "R73") (pin "1") (pinfunction "1_1") (pintype "passive"))
      (node (ref "U$100") (pin "JP2.4") (pinfunction "D2_JP2.4") (pintype "bidirectional"))
      (node (ref "U5") (pin "2") (pinfunction "S_2") (pintype "bidirectional"))
    )
    (net (code "3") (name "/(5)-SHCP") (class "Default")
      (node (ref "R71") (pin "1") (pinfunction "1_1") (pintype "passive"))
      (node (ref "U$100") (pin "JP2.3") (pinfunction "D1_JP2.3") (pintype "bidirectional"))
      (node (ref "U4") (pin "2") (pinfunction "S_2") (pintype "bidirectional"))
    )
    (net (code "4") (name "/3.3V") (class "Default")
      (node (ref "R66") (pin "2") (pinfunction "2_2") (pintype "passive"))
      (node (ref "R68") (pin "2") (pinfunction "2_2") (pintype "passive"))
      (node (ref "R70") (pin "1") (pinfunction "1_1") (pintype "passive"))
      (node (ref "R71") (pin "2") (pinfunction "2_2") (pintype "passive"))
      (node (ref "R73") (pin "2") (pinfunction "2_2") (pintype "passive"))
      (node (ref "R75") (pin "2") (pinfunction "2_2") (pintype "passive"))
      (node (ref "U$100") (pin "JP1.8") (pinfunction "3V3_JP1.8") (pintype "power_in"))
      (node (ref "U1") (pin "1") (pinfunction "G_1") (pintype "bidirectional"))
      (node (ref "U2") (pin "1") (pinfunction "G_1") (pintype "bidirectional"))
      (node (ref "U3") (pin "1") (pinfunction "G_1") (pintype "bidirectional"))
      (node (ref "U4") (pin "1") (pinfunction "G_1") (pintype "bidirectional"))
      (node (ref "U5") (pin "1") (pinfunction "G_1") (pintype "bidirectional"))
      (node (ref "U6") (pin "1") (pinfunction "G_1") (pintype "bidirectional"))
    )
    (net (code "5") (name "/CP") (class "Default")
      (node (ref "R66") (pin "1") (pinfunction "1_1") (pintype "passive"))
      (node (ref "U$100") (pin "JP1.4") (pinfunction "D5_JP1.4") (pintype "bidirectional"))
      (node (ref "U1") (pin "2") (pinfunction "S_2") (pintype "bidirectional"))
    )
    (net (code "6") (name "/CP-(2)") (class "Default")
      (node (ref "IC5") (pin "2") (pinfunction "CLK_2") (pintype "input"))
      (node (ref "IC6") (pin "2") (pinfunction "CLK_2") (pintype "input"))
      (node (ref "IC7") (pin "2") (pinfunction "CLK_2") (pintype "input"))
      (node (ref "IC8") (pin "2") (pinfunction "CLK_2") (pintype "input"))
      (node (ref "R65") (pin "1") (pinfunction "1_1") (pintype "passive"))
      (node (ref "U1") (pin "3") (pinfunction "D_3") (pintype "bidirectional"))
    )
    (net (code "7") (name "/DS-(14)") (class "Default")
      (node (ref "IC1") (pin "14") (pinfunction "SER_14") (pintype "input"))
      (node (ref "R76") (pin "1") (pinfunction "1_1") (pintype "passive"))
      (node (ref "U6") (pin "3") (pinfunction "D_3") (pintype "bidirectional"))
    )
    (net (code "8") (name "/PL") (class "Default")
      (node (ref "R68") (pin "1") (pinfunction "1_1") (pintype "passive"))
      (node (ref "U$100") (pin "JP1.5") (pinfunction "D6_JP1.5") (pintype "bidirectional"))
      (node (ref "U2") (pin "2") (pinfunction "S_2") (pintype "bidirectional"))
    )
    (net (code "9") (name "/PL-(1)") (class "Default")
      (node (ref "IC5") (pin "1") (pinfunction "SH/~{LD}_1") (pintype "input"))
      (node (ref "IC6") (pin "1") (pinfunction "SH/~{LD}_1") (pintype "input"))
      (node (ref "IC7") (pin "1") (pinfunction "SH/~{LD}_1") (pintype "input"))
      (node (ref "IC8") (pin "1") (pinfunction "SH/~{LD}_1") (pintype "input"))
      (node (ref "R67") (pin "1") (pinfunction "1_1") (pintype "passive"))
      (node (ref "U2") (pin "3") (pinfunction "D_3") (pintype "bidirectional"))
    )
    (net (code "10") (name "/Q7") (class "Default")
      (node (ref "R70") (pin "2") (pinfunction "2_2") (pintype "passive"))
      (node (ref "U$100") (pin "JP1.6") (pinfunction "D7_JP1.6") (pintype "bidirectional"))
      (node (ref "U3") (pin "2") (pinfunction "S_2") (pintype "bidirectional"))
    )
    (net (code "11") (name "/Q7-(9)") (class "Default")
      (node (ref "IC8") (pin "9") (pinfunction "QH_9") (pintype "output"))
      (node (ref "R69") (pin "1") (pinfunction "1_1") (pintype "passive"))
      (node (ref "U3") (pin "3") (pinfunction "D_3") (pintype "bidirectional"))
    )
    (net (code "12") (name "/Q7-DS-1") (class "Default")
      (node (ref "IC5") (pin "9") (pinfunction "QH_9") (pintype "output"))
      (node (ref "IC6") (pin "10") (pinfunction "SER_10") (pintype "input"))
    )
    (net (code "13") (name "/Q7-DS-2") (class "Default")
      (node (ref "IC6") (pin "9") (pinfunction "QH_9") (pintype "output"))
      (node (ref "IC7") (pin "10") (pinfunction "SER_10") (pintype "input"))
    )
    (net (code "14") (name "/Q7-DS-3") (class "Default")
      (node (ref "IC7") (pin "9") (pinfunction "QH_9") (pintype "output"))
      (node (ref "IC8") (pin "10") (pinfunction "SER_10") (pintype "input"))
    )
    (net (code "15") (name "/SHCP-(11)") (class "Default")
      (node (ref "IC1") (pin "11") (pinfunction "SCK_11") (pintype "input"))
      (node (ref "IC2") (pin "11") (pinfunction "SCK_11") (pintype "input"))
      (node (ref "IC3") (pin "11") (pinfunction "SCK_11") (pintype "input"))
      (node (ref "IC4") (pin "11") (pinfunction "SCK_11") (pintype "input"))
      (node (ref "R72") (pin "1") (pinfunction "1_1") (pintype "passive"))
      (node (ref "U4") (pin "3") (pinfunction "D_3") (pintype "bidirectional"))
    )
    (net (code "16") (name "/STCP-(12)") (class "Default")
      (node (ref "IC1") (pin "12") (pinfunction "RCK_12") (pintype "input"))
      (node (ref "IC2") (pin "12") (pinfunction "RCK_12") (pintype "input"))
      (node (ref "IC3") (pin "12") (pinfunction "RCK_12") (pintype "input"))
      (node (ref "IC4") (pin "12") (pinfunction "RCK_12") (pintype "input"))
      (node (ref "R74") (pin "1") (pinfunction "1_1") (pintype "passive"))
      (node (ref "U5") (pin "3") (pinfunction "D_3") (pintype "bidirectional"))
    )
    (net (code "17") (name "GND") (class "Default")
      (node (ref "IC1") (pin "13") (pinfunction "G_13") (pintype "input"))
      (node (ref "IC2") (pin "13") (pinfunction "G_13") (pintype "input"))
      (node (ref "IC3") (pin "13") (pinfunction "G_13") (pintype "input"))
      (node (ref "IC4") (pin "13") (pinfunction "G_13") (pintype "input"))
      (node (ref "IC5") (pin "15") (pinfunction "INH_15") (pintype "input"))
      (node (ref "IC6") (pin "15") (pinfunction "INH_15") (pintype "input"))
      (node (ref "IC7") (pin "15") (pinfunction "INH_15") (pintype "input"))
      (node (ref "IC8") (pin "15") (pinfunction "INH_15") (pintype "input"))
      (node (ref "OK1") (pin "2") (pinfunction "C_2") (pintype "passive"))
      (node (ref "OK1") (pin "4") (pinfunction "C_4") (pintype "passive"))
      (node (ref "OK1") (pin "6") (pinfunction "C_6") (pintype "passive"))
      (node (ref "OK1") (pin "8") (pinfunction "C_8") (pintype "passive"))
      (node (ref "OK2") (pin "2") (pinfunction "C_2") (pintype "passive"))
      (node (ref "OK2") (pin "4") (pinfunction "C_4") (pintype "passive"))
      (node (ref "OK2") (pin "6") (pinfunction "C_6") (pintype "passive"))
      (node (ref "OK2") (pin "8") (pinfunction "C_8") (pintype "passive"))
      (node (ref "OK3") (pin "2") (pinfunction "C_2") (pintype "passive"))
      (node (ref "OK3") (pin "4") (pinfunction "C_4") (pintype "passive"))
      (node (ref "OK3") (pin "6") (pinfunction "C_6") (pintype "passive"))
      (node (ref "OK3") (pin "8") (pinfunction "C_8") (pintype "passive"))
      (node (ref "OK4") (pin "2") (pinfunction "C_2") (pintype "passive"))
      (node (ref "OK4") (pin "4") (pinfunction "C_4") (pintype "passive"))
      (node (ref "OK4") (pin "6") (pinfunction "C_6") (pintype "passive"))
      (node (ref "OK4") (pin "8") (pinfunction "C_8") (pintype "passive"))
      (node (ref "OK5") (pin "2") (pinfunction "C_2") (pintype "passive"))
      (node (ref "OK5") (pin "4") (pinfunction "C_4") (pintype "passive"))
      (node (ref "OK5") (pin "6") (pinfunction "C_6") (pintype "passive"))
      (node (ref "OK5") (pin "8") (pinfunction "C_8") (pintype "passive"))
      (node (ref "OK6") (pin "2") (pinfunction "C_2") (pintype "passive"))
      (node (ref "OK6") (pin "4") (pinfunction "C_4") (pintype "passive"))
      (node (ref "OK6") (pin "6") (pinfunction "C_6") (pintype "passive"))
      (node (ref "OK6") (pin "8") (pinfunction "C_8") (pintype "passive"))
      (node (ref "OK7") (pin "2") (pinfunction "C_2") (pintype "passive"))
      (node (ref "OK7") (pin "4") (pinfunction "C_4") (pintype "passive"))
      (node (ref "OK7") (pin "6") (pinfunction "C_6") (pintype "passive"))
      (node (ref "OK7") (pin "8") (pinfunction "C_8") (pintype "passive"))
      (node (ref "OK8") (pin "2") (pinfunction "C_2") (pintype "passive"))
      (node (ref "OK8") (pin "4") (pinfunction "C_4") (pintype "passive"))
      (node (ref "OK8") (pin "6") (pinfunction "C_6") (pintype "passive"))
      (node (ref "OK8") (pin "8") (pinfunction "C_8") (pintype "passive"))
      (node (ref "R33") (pin "2") (pinfunction "2_2") (pintype "passive"))
      (node (ref "R34") (pin "2") (pinfunction "2_2") (pintype "passive"))
      (node (ref "R35") (pin "2") (pinfunction "2_2") (pintype "passive"))
      (node (ref "R36") (pin "2") (pinfunction "2_2") (pintype "passive"))
      (node (ref "R37") (pin "2") (pinfunction "2_2") (pintype "passive"))
      (node (ref "R38") (pin "2") (pinfunction "2_2") (pintype "passive"))
      (node (ref "R39") (pin "2") (pinfunction "2_2") (pintype "passive"))
      (node (ref "R40") (pin "2") (pinfunction "2_2") (pintype "passive"))
      (node (ref "R41") (pin "2") (pinfunction "2_2") (pintype "passive"))
      (node (ref "R42") (pin "2") (pinfunction "2_2") (pintype "passive"))
      (node (ref "R43") (pin "2") (pinfunction "2_2") (pintype "passive"))
      (node (ref "R44") (pin "2") (pinfunction "2_2") (pintype "passive"))
      (node (ref "R45") (pin "2") (pinfunction "2_2") (pintype "passive"))
      (node (ref "R46") (pin "2") (pinfunction "2_2") (pintype "passive"))
      (node (ref "R47") (pin "2") (pinfunction "2_2") (pintype "passive"))
      (node (ref "R48") (pin "2") (pinfunction "2_2") (pintype "passive"))
      (node (ref "R49") (pin "2") (pinfunction "2_2") (pintype "passive"))
      (node (ref "R50") (pin "2") (pinfunction "2_2") (pintype "passive"))
      (node (ref "R51") (pin "2") (pinfunction "2_2") (pintype "passive"))
      (node (ref "R52") (pin "2") (pinfunction "2_2") (pintype "passive"))
      (node (ref "R53") (pin "2") (pinfunction "2_2") (pintype "passive"))
      (node (ref "R54") (pin "2") (pinfunction "2_2") (pintype "passive"))
      (node (ref "R55") (pin "2") (pinfunction "2_2") (pintype "passive"))
      (node (ref "R56") (pin "2") (pinfunction "2_2") (pintype "passive"))
      (node (ref "R57") (pin "2") (pinfunction "2_2") (pintype "passive"))
      (node (ref "R58") (pin "2") (pinfunction "2_2") (pintype "passive"))
      (node (ref "R59") (pin "2") (pinfunction "2_2") (pintype "passive"))
      (node (ref "R60") (pin "2") (pinfunction "2_2") (pintype "passive"))
      (node (ref "R61") (pin "2") (pinfunction "2_2") (pintype "passive"))
      (node (ref "R62") (pin "2") (pinfunction "2_2") (pintype "passive"))
      (node (ref "R63") (pin "2") (pinfunction "2_2") (pintype "passive"))
      (node (ref "R64") (pin "2") (pinfunction "2_2") (pintype "passive"))
      (node (ref "U$100") (pin "JP2.7") (pinfunction "GND_JP2.7") (pintype "power_in"))
    )
    (net (code "18") (name "Net-(IC1A-QA)") (class "Default")
      (node (ref "IC1") (pin "15") (pinfunction "QA_15") (pintype "tri_state"))
      (node (ref "R1") (pin "1") (pinfunction "1_1") (pintype "passive"))
    )
    (net (code "19") (name "Net-(IC1A-QB)") (class "Default")
      (node (ref "IC1") (pin "1") (pinfunction "QB_1") (pintype "tri_state"))
      (node (ref "R2") (pin "1") (pinfunction "1_1") (pintype "passive"))
    )
    (net (code "20") (name "Net-(IC1A-QC)") (class "Default")
      (node (ref "IC1") (pin "2") (pinfunction "QC_2") (pintype "tri_state"))
      (node (ref "R3") (pin "1") (pinfunction "1_1") (pintype "passive"))
    )
    (net (code "21") (name "Net-(IC1A-QD)") (class "Default")
      (node (ref "IC1") (pin "3") (pinfunction "QD_3") (pintype "tri_state"))
      (node (ref "R4") (pin "1") (pinfunction "1_1") (pintype "passive"))
    )
    (net (code "22") (name "Net-(IC1A-QE)") (class "Default")
      (node (ref "IC1") (pin "4") (pinfunction "QE_4") (pintype "tri_state"))
      (node (ref "R5") (pin "1") (pinfunction "1_1") (pintype "passive"))
    )
    (net (code "23") (name "Net-(IC1A-QF)") (class "Default")
      (node (ref "IC1") (pin "5") (pinfunction "QF_5") (pintype "tri_state"))
      (node (ref "R6") (pin "1") (pinfunction "1_1") (pintype "passive"))
    )
    (net (code "24") (name "Net-(IC1A-QG)") (class "Default")
      (node (ref "IC1") (pin "6") (pinfunction "QG_6") (pintype "tri_state"))
      (node (ref "R7") (pin "1") (pinfunction "1_1") (pintype "passive"))
    )
    (net (code "25") (name "Net-(IC1A-QH)") (class "Default")
      (node (ref "IC1") (pin "7") (pinfunction "QH_7") (pintype "tri_state"))
      (node (ref "R8") (pin "1") (pinfunction "1_1") (pintype "passive"))
    )
    (net (code "26") (name "Net-(IC1A-QH*)") (class "Default")
      (node (ref "IC1") (pin "9") (pinfunction "QH*_9") (pintype "tri_state"))
      (node (ref "IC2") (pin "14") (pinfunction "SER_14") (pintype "input"))
    )
    (net (code "27") (name "Net-(IC2A-QA)") (class "Default")
      (node (ref "IC2") (pin "15") (pinfunction "QA_15") (pintype "tri_state"))
      (node (ref "R9") (pin "1") (pinfunction "1_1") (pintype "passive"))
    )
    (net (code "28") (name "Net-(IC2A-QB)") (class "Default")
      (node (ref "IC2") (pin "1") (pinfunction "QB_1") (pintype "tri_state"))
      (node (ref "R10") (pin "1") (pinfunction "1_1") (pintype "passive"))
    )
    (net (code "29") (name "Net-(IC2A-QC)") (class "Default")
      (node (ref "IC2") (pin "2") (pinfunction "QC_2") (pintype "tri_state"))
      (node (ref "R11") (pin "1") (pinfunction "1_1") (pintype "passive"))
    )
    (net (code "30") (name "Net-(IC2A-QD)") (class "Default")
      (node (ref "IC2") (pin "3") (pinfunction "QD_3") (pintype "tri_state"))
      (node (ref "R12") (pin "1") (pinfunction "1_1") (pintype "passive"))
    )
    (net (code "31") (name "Net-(IC2A-QE)") (class "Default")
      (node (ref "IC2") (pin "4") (pinfunction "QE_4") (pintype "tri_state"))
      (node (ref "R13") (pin "1") (pinfunction "1_1") (pintype "passive"))
    )
    (net (code "32") (name "Net-(IC2A-QF)") (class "Default")
      (node (ref "IC2") (pin "5") (pinfunction "QF_5") (pintype "tri_state"))
      (node (ref "R14") (pin "1") (pinfunction "1_1") (pintype "passive"))
    )
    (net (code "33") (name "Net-(IC2A-QG)") (class "Default")
      (node (ref "IC2") (pin "6") (pinfunction "QG_6") (pintype "tri_state"))
      (node (ref "R15") (pin "1") (pinfunction "1_1") (pintype "passive"))
    )
    (net (code "34") (name "Net-(IC2A-QH)") (class "Default")
      (node (ref "IC2") (pin "7") (pinfunction "QH_7") (pintype "tri_state"))
      (node (ref "R16") (pin "1") (pinfunction "1_1") (pintype "passive"))
    )
    (net (code "35") (name "Net-(IC2A-QH*)") (class "Default")
      (node (ref "IC2") (pin "9") (pinfunction "QH*_9") (pintype "tri_state"))
      (node (ref "IC3") (pin "14") (pinfunction "SER_14") (pintype "input"))
    )
    (net (code "36") (name "Net-(IC3A-QA)") (class "Default")
      (node (ref "IC3") (pin "15") (pinfunction "QA_15") (pintype "tri_state"))
      (node (ref "R17") (pin "1") (pinfunction "1_1") (pintype "passive"))
    )
    (net (code "37") (name "Net-(IC3A-QB)") (class "Default")
      (node (ref "IC3") (pin "1") (pinfunction "QB_1") (pintype "tri_state"))
      (node (ref "R18") (pin "1") (pinfunction "1_1") (pintype "passive"))
    )
    (net (code "38") (name "Net-(IC3A-QC)") (class "Default")
      (node (ref "IC3") (pin "2") (pinfunction "QC_2") (pintype "tri_state"))
      (node (ref "R19") (pin "1") (pinfunction "1_1") (pintype "passive"))
    )
    (net (code "39") (name "Net-(IC3A-QD)") (class "Default")
      (node (ref "IC3") (pin "3") (pinfunction "QD_3") (pintype "tri_state"))
      (node (ref "R20") (pin "1") (pinfunction "1_1") (pintype "passive"))
    )
    (net (code "40") (name "Net-(IC3A-QE)") (class "Default")
      (node (ref "IC3") (pin "4") (pinfunction "QE_4") (pintype "tri_state"))
      (node (ref "R21") (pin "1") (pinfunction "1_1") (pintype "passive"))
    )
    (net (code "41") (name "Net-(IC3A-QF)") (class "Default")
      (node (ref "IC3") (pin "5") (pinfunction "QF_5") (pintype "tri_state"))
      (node (ref "R22") (pin "1") (pinfunction "1_1") (pintype "passive"))
    )
    (net (code "42") (name "Net-(IC3A-QG)") (class "Default")
      (node (ref "IC3") (pin "6") (pinfunction "QG_6") (pintype "tri_state"))
      (node (ref "R23") (pin "1") (pinfunction "1_1") (pintype "passive"))
    )
    (net (code "43") (name "Net-(IC3A-QH)") (class "Default")
      (node (ref "IC3") (pin "7") (pinfunction "QH_7") (pintype "tri_state"))
      (node (ref "R24") (pin "1") (pinfunction "1_1") (pintype "passive"))
    )
    (net (code "44") (name "Net-(IC3A-QH*)") (class "Default")
      (node (ref "IC3") (pin "9") (pinfunction "QH*_9") (pintype "tri_state"))
      (node (ref "IC4") (pin "14") (pinfunction "SER_14") (pintype "input"))
    )
    (net (code "45") (name "Net-(IC4A-QA)") (class "Default")
      (node (ref "IC4") (pin "15") (pinfunction "QA_15") (pintype "tri_state"))
      (node (ref "R25") (pin "1") (pinfunction "1_1") (pintype "passive"))
    )
    (net (code "46") (name "Net-(IC4A-QB)") (class "Default")
      (node (ref "IC4") (pin "1") (pinfunction "QB_1") (pintype "tri_state"))
      (node (ref "R26") (pin "1") (pinfunction "1_1") (pintype "passive"))
    )
    (net (code "47") (name "Net-(IC4A-QC)") (class "Default")
      (node (ref "IC4") (pin "2") (pinfunction "QC_2") (pintype "tri_state"))
      (node (ref "R27") (pin "1") (pinfunction "1_1") (pintype "passive"))
    )
    (net (code "48") (name "Net-(IC4A-QD)") (class "Default")
      (node (ref "IC4") (pin "3") (pinfunction "QD_3") (pintype "tri_state"))
      (node (ref "R28") (pin "1") (pinfunction "1_1") (pintype "passive"))
    )
    (net (code "49") (name "Net-(IC4A-QE)") (class "Default")
      (node (ref "IC4") (pin "4") (pinfunction "QE_4") (pintype "tri_state"))
      (node (ref "R29") (pin "1") (pinfunction "1_1") (pintype "passive"))
    )
    (net (code "50") (name "Net-(IC4A-QF)") (class "Default")
      (node (ref "IC4") (pin "5") (pinfunction "QF_5") (pintype "tri_state"))
      (node (ref "R30") (pin "1") (pinfunction "1_1") (pintype "passive"))
    )
    (net (code "51") (name "Net-(IC4A-QG)") (class "Default")
      (node (ref "IC4") (pin "6") (pinfunction "QG_6") (pintype "tri_state"))
      (node (ref "R31") (pin "1") (pinfunction "1_1") (pintype "passive"))
    )
    (net (code "52") (name "Net-(IC4A-QH)") (class "Default")
      (node (ref "IC4") (pin "7") (pinfunction "QH_7") (pintype "tri_state"))
      (node (ref "R32") (pin "1") (pinfunction "1_1") (pintype "passive"))
    )
    (net (code "53") (name "Net-(IC5A-A)") (class "Default")
      (node (ref "IC5") (pin "11") (pinfunction "A_11") (pintype "input"))
      (node (ref "R33") (pin "1") (pinfunction "1_1") (pintype "passive"))
      (node (ref "U$9") (pin "1") (pinfunction "1_1") (pintype "bidirectional"))
    )
    (net (code "54") (name "Net-(IC5A-B)") (class "Default")
      (node (ref "IC5") (pin "12") (pinfunction "B_12") (pintype "input"))
      (node (ref "R34") (pin "1") (pinfunction "1_1") (pintype "passive"))
      (node (ref "U$9") (pin "2") (pinfunction "2_2") (pintype "bidirectional"))
    )
    (net (code "55") (name "Net-(IC5A-C)") (class "Default")
      (node (ref "IC5") (pin "13") (pinfunction "C_13") (pintype "input"))
      (node (ref "R35") (pin "1") (pinfunction "1_1") (pintype "passive"))
      (node (ref "U$9") (pin "3") (pinfunction "3_3") (pintype "bidirectional"))
    )
    (net (code "56") (name "Net-(IC5A-D)") (class "Default")
      (node (ref "IC5") (pin "14") (pinfunction "D_14") (pintype "input"))
      (node (ref "R36") (pin "1") (pinfunction "1_1") (pintype "passive"))
      (node (ref "U$9") (pin "4") (pinfunction "4_4") (pintype "bidirectional"))
    )
    (net (code "57") (name "Net-(IC5A-E)") (class "Default")
      (node (ref "IC5") (pin "3") (pinfunction "E_3") (pintype "input"))
      (node (ref "R37") (pin "1") (pinfunction "1_1") (pintype "passive"))
      (node (ref "U$10") (pin "1") (pinfunction "1_1") (pintype "bidirectional"))
    )
    (net (code "58") (name "Net-(IC5A-F)") (class "Default")
      (node (ref "IC5") (pin "4") (pinfunction "F_4") (pintype "input"))
      (node (ref "R38") (pin "1") (pinfunction "1_1") (pintype "passive"))
      (node (ref "U$10") (pin "2") (pinfunction "2_2") (pintype "bidirectional"))
    )
    (net (code "59") (name "Net-(IC5A-G)") (class "Default")
      (node (ref "IC5") (pin "5") (pinfunction "G_5") (pintype "input"))
      (node (ref "R39") (pin "1") (pinfunction "1_1") (pintype "passive"))
      (node (ref "U$10") (pin "3") (pinfunction "3_3") (pintype "bidirectional"))
    )
    (net (code "60") (name "Net-(IC5A-H)") (class "Default")
      (node (ref "IC5") (pin "6") (pinfunction "H_6") (pintype "input"))
      (node (ref "R40") (pin "1") (pinfunction "1_1") (pintype "passive"))
      (node (ref "U$10") (pin "4") (pinfunction "4_4") (pintype "bidirectional"))
    )
    (net (code "61") (name "Net-(IC6A-A)") (class "Default")
      (node (ref "IC6") (pin "11") (pinfunction "A_11") (pintype "input"))
      (node (ref "R41") (pin "1") (pinfunction "1_1") (pintype "passive"))
      (node (ref "U$11") (pin "1") (pinfunction "1_1") (pintype "bidirectional"))
    )
    (net (code "62") (name "Net-(IC6A-B)") (class "Default")
      (node (ref "IC6") (pin "12") (pinfunction "B_12") (pintype "input"))
      (node (ref "R42") (pin "1") (pinfunction "1_1") (pintype "passive"))
      (node (ref "U$11") (pin "2") (pinfunction "2_2") (pintype "bidirectional"))
    )
    (net (code "63") (name "Net-(IC6A-C)") (class "Default")
      (node (ref "IC6") (pin "13") (pinfunction "C_13") (pintype "input"))
      (node (ref "R43") (pin "1") (pinfunction "1_1") (pintype "passive"))
      (node (ref "U$11") (pin "3") (pinfunction "3_3") (pintype "bidirectional"))
    )
    (net (code "64") (name "Net-(IC6A-D)") (class "Default")
      (node (ref "IC6") (pin "14") (pinfunction "D_14") (pintype "input"))
      (node (ref "R44") (pin "1") (pinfunction "1_1") (pintype "passive"))
      (node (ref "U$11") (pin "4") (pinfunction "4_4") (pintype "bidirectional"))
    )
    (net (code "65") (name "Net-(IC6A-E)") (class "Default")
      (node (ref "IC6") (pin "3") (pinfunction "E_3") (pintype "input"))
      (node (ref "R45") (pin "1") (pinfunction "1_1") (pintype "passive"))
      (node (ref "U$12") (pin "1") (pinfunction "1_1") (pintype "bidirectional"))
    )
    (net (code "66") (name "Net-(IC6A-F)") (class "Default")
      (node (ref "IC6") (pin "4") (pinfunction "F_4") (pintype "input"))
      (node (ref "R46") (pin "1") (pinfunction "1_1") (pintype "passive"))
      (node (ref "U$12") (pin "2") (pinfunction "2_2") (pintype "bidirectional"))
    )
    (net (code "67") (name "Net-(IC6A-G)") (class "Default")
      (node (ref "IC6") (pin "5") (pinfunction "G_5") (pintype "input"))
      (node (ref "R47") (pin "1") (pinfunction "1_1") (pintype "passive"))
      (node (ref "U$12") (pin "3") (pinfunction "3_3") (pintype "bidirectional"))
    )
    (net (code "68") (name "Net-(IC6A-H)") (class "Default")
      (node (ref "IC6") (pin "6") (pinfunction "H_6") (pintype "input"))
      (node (ref "R48") (pin "1") (pinfunction "1_1") (pintype "passive"))
      (node (ref "U$12") (pin "4") (pinfunction "4_4") (pintype "bidirectional"))
    )
    (net (code "69") (name "Net-(IC7A-A)") (class "Default")
      (node (ref "IC7") (pin "11") (pinfunction "A_11") (pintype "input"))
      (node (ref "R49") (pin "1") (pinfunction "1_1") (pintype "passive"))
      (node (ref "U$13") (pin "1") (pinfunction "1_1") (pintype "bidirectional"))
    )
    (net (code "70") (name "Net-(IC7A-B)") (class "Default")
      (node (ref "IC7") (pin "12") (pinfunction "B_12") (pintype "input"))
      (node (ref "R50") (pin "1") (pinfunction "1_1") (pintype "passive"))
      (node (ref "U$13") (pin "2") (pinfunction "2_2") (pintype "bidirectional"))
    )
    (net (code "71") (name "Net-(IC7A-C)") (class "Default")
      (node (ref "IC7") (pin "13") (pinfunction "C_13") (pintype "input"))
      (node (ref "R51") (pin "1") (pinfunction "1_1") (pintype "passive"))
      (node (ref "U$13") (pin "3") (pinfunction "3_3") (pintype "bidirectional"))
    )
    (net (code "72") (name "Net-(IC7A-D)") (class "Default")
      (node (ref "IC7") (pin "14") (pinfunction "D_14") (pintype "input"))
      (node (ref "R52") (pin "1") (pinfunction "1_1") (pintype "passive"))
      (node (ref "U$13") (pin "4") (pinfunction "4_4") (pintype "bidirectional"))
    )
    (net (code "73") (name "Net-(IC7A-E)") (class "Default")
      (node (ref "IC7") (pin "3") (pinfunction "E_3") (pintype "input"))
      (node (ref "R53") (pin "1") (pinfunction "1_1") (pintype "passive"))
      (node (ref "U$127") (pin "1") (pinfunction "1_1") (pintype "bidirectional"))
    )
    (net (code "74") (name "Net-(IC7A-F)") (class "Default")
      (node (ref "IC7") (pin "4") (pinfunction "F_4") (pintype "input"))
      (node (ref "R54") (pin "1") (pinfunction "1_1") (pintype "passive"))
      (node (ref "U$127") (pin "2") (pinfunction "2_2") (pintype "bidirectional"))
    )
    (net (code "75") (name "Net-(IC7A-G)") (class "Default")
      (node (ref "IC7") (pin "5") (pinfunction "G_5") (pintype "input"))
      (node (ref "R55") (pin "1") (pinfunction "1_1") (pintype "passive"))
      (node (ref "U$127") (pin "3") (pinfunction "3_3") (pintype "bidirectional"))
    )
    (net (code "76") (name "Net-(IC7A-H)") (class "Default")
      (node (ref "IC7") (pin "6") (pinfunction "H_6") (pintype "input"))
      (node (ref "R56") (pin "1") (pinfunction "1_1") (pintype "passive"))
      (node (ref "U$127") (pin "4") (pinfunction "4_4") (pintype "bidirectional"))
    )
    (net (code "77") (name "Net-(IC8A-A)") (class "Default")
      (node (ref "IC8") (pin "11") (pinfunction "A_11") (pintype "input"))
      (node (ref "R57") (pin "1") (pinfunction "1_1") (pintype "passive"))
      (node (ref "U$15") (pin "1") (pinfunction "1_1") (pintype "bidirectional"))
    )
    (net (code "78") (name "Net-(IC8A-B)") (class "Default")
      (node (ref "IC8") (pin "12") (pinfunction "B_12") (pintype "input"))
      (node (ref "R58") (pin "1") (pinfunction "1_1") (pintype "passive"))
      (node (ref "U$15") (pin "2") (pinfunction "2_2") (pintype "bidirectional"))
    )
    (net (code "79") (name "Net-(IC8A-C)") (class "Default")
      (node (ref "IC8") (pin "13") (pinfunction "C_13") (pintype "input"))
      (node (ref "R59") (pin "1") (pinfunction "1_1") (pintype "passive"))
      (node (ref "U$15") (pin "3") (pinfunction "3_3") (pintype "bidirectional"))
    )
    (net (code "80") (name "Net-(IC8A-D)") (class "Default")
      (node (ref "IC8") (pin "14") (pinfunction "D_14") (pintype "input"))
      (node (ref "R60") (pin "1") (pinfunction "1_1") (pintype "passive"))
      (node (ref "U$15") (pin "4") (pinfunction "4_4") (pintype "bidirectional"))
    )
    (net (code "81") (name "Net-(IC8A-E)") (class "Default")
      (node (ref "IC8") (pin "3") (pinfunction "E_3") (pintype "input"))
      (node (ref "R61") (pin "1") (pinfunction "1_1") (pintype "passive"))
      (node (ref "U$16") (pin "1") (pinfunction "1_1") (pintype "bidirectional"))
    )
    (net (code "82") (name "Net-(IC8A-F)") (class "Default")
      (node (ref "IC8") (pin "4") (pinfunction "F_4") (pintype "input"))
      (node (ref "R62") (pin "1") (pinfunction "1_1") (pintype "passive"))
      (node (ref "U$16") (pin "2") (pinfunction "2_2") (pintype "bidirectional"))
    )
    (net (code "83") (name "Net-(IC8A-G)") (class "Default")
      (node (ref "IC8") (pin "5") (pinfunction "G_5") (pintype "input"))
      (node (ref "R63") (pin "1") (pinfunction "1_1") (pintype "passive"))
      (node (ref "U$16") (pin "3") (pinfunction "3_3") (pintype "bidirectional"))
    )
    (net (code "84") (name "Net-(IC8A-H)") (class "Default")
      (node (ref "IC8") (pin "6") (pinfunction "H_6") (pintype "input"))
      (node (ref "R64") (pin "1") (pinfunction "1_1") (pintype "passive"))
      (node (ref "U$16") (pin "4") (pinfunction "4_4") (pintype "bidirectional"))
    )
    (net (code "85") (name "Net-(OK1A-A)") (class "Default")
      (node (ref "OK1") (pin "1") (pinfunction "A_1") (pintype "passive"))
      (node (ref "R1") (pin "2") (pinfunction "2_2") (pintype "passive"))
    )
    (net (code "86") (name "Net-(OK1A-EMIT)") (class "Default")
      (node (ref "OK1") (pin "15") (pinfunction "EMIT_15") (pintype "passive"))
      (node (ref "U$1") (pin "1") (pinfunction "1_1") (pintype "bidirectional"))
    )
    (net (code "87") (name "Net-(OK1B-A)") (class "Default")
      (node (ref "OK1") (pin "3") (pinfunction "A_3") (pintype "passive"))
      (node (ref "R2") (pin "2") (pinfunction "2_2") (pintype "passive"))
    )
    (net (code "88") (name "Net-(OK1B-EMIT)") (class "Default")
      (node (ref "OK1") (pin "13") (pinfunction "EMIT_13") (pintype "passive"))
      (node (ref "U$1") (pin "2") (pinfunction "2_2") (pintype "bidirectional"))
    )
    (net (code "89") (name "Net-(OK1C-A)") (class "Default")
      (node (ref "OK1") (pin "5") (pinfunction "A_5") (pintype "passive"))
      (node (ref "R3") (pin "2") (pinfunction "2_2") (pintype "passive"))
    )
    (net (code "90") (name "Net-(OK1C-EMIT)") (class "Default")
      (node (ref "OK1") (pin "11") (pinfunction "EMIT_11") (pintype "passive"))
      (node (ref "U$1") (pin "3") (pinfunction "3_3") (pintype "bidirectional"))
    )
    (net (code "91") (name "Net-(OK1D-A)") (class "Default")
      (node (ref "OK1") (pin "7") (pinfunction "A_7") (pintype "passive"))
      (node (ref "R4") (pin "2") (pinfunction "2_2") (pintype "passive"))
    )
    (net (code "92") (name "Net-(OK1D-EMIT)") (class "Default")
      (node (ref "OK1") (pin "9") (pinfunction "EMIT_9") (pintype "passive"))
      (node (ref "U$1") (pin "4") (pinfunction "4_4") (pintype "bidirectional"))
    )
    (net (code "93") (name "Net-(OK2A-A)") (class "Default")
      (node (ref "OK2") (pin "1") (pinfunction "A_1") (pintype "passive"))
      (node (ref "R5") (pin "2") (pinfunction "2_2") (pintype "passive"))
    )
    (net (code "94") (name "Net-(OK2A-EMIT)") (class "Default")
      (node (ref "OK2") (pin "15") (pinfunction "EMIT_15") (pintype "passive"))
      (node (ref "U$2") (pin "1") (pinfunction "1_1") (pintype "bidirectional"))
    )
    (net (code "95") (name "Net-(OK2B-A)") (class "Default")
      (node (ref "OK2") (pin "3") (pinfunction "A_3") (pintype "passive"))
      (node (ref "R6") (pin "2") (pinfunction "2_2") (pintype "passive"))
    )
    (net (code "96") (name "Net-(OK2B-EMIT)") (class "Default")
      (node (ref "OK2") (pin "13") (pinfunction "EMIT_13") (pintype "passive"))
      (node (ref "U$2") (pin "2") (pinfunction "2_2") (pintype "bidirectional"))
    )
    (net (code "97") (name "Net-(OK2C-A)") (class "Default")
      (node (ref "OK2") (pin "5") (pinfunction "A_5") (pintype "passive"))
      (node (ref "R7") (pin "2") (pinfunction "2_2") (pintype "passive"))
    )
    (net (code "98") (name "Net-(OK2C-EMIT)") (class "Default")
      (node (ref "OK2") (pin "11") (pinfunction "EMIT_11") (pintype "passive"))
      (node (ref "U$2") (pin "3") (pinfunction "3_3") (pintype "bidirectional"))
    )
    (net (code "99") (name "Net-(OK2D-A)") (class "Default")
      (node (ref "OK2") (pin "7") (pinfunction "A_7") (pintype "passive"))
      (node (ref "R8") (pin "2") (pinfunction "2_2") (pintype "passive"))
    )
    (net (code "100") (name "Net-(OK2D-EMIT)") (class "Default")
      (node (ref "OK2") (pin "9") (pinfunction "EMIT_9") (pintype "passive"))
      (node (ref "U$2") (pin "4") (pinfunction "4_4") (pintype "bidirectional"))
    )
    (net (code "101") (name "Net-(OK3A-A)") (class "Default")
      (node (ref "OK3") (pin "1") (pinfunction "A_1") (pintype "passive"))
      (node (ref "R9") (pin "2") (pinfunction "2_2") (pintype "passive"))
    )
    (net (code "102") (name "Net-(OK3A-EMIT)") (class "Default")
      (node (ref "OK3") (pin "15") (pinfunction "EMIT_15") (pintype "passive"))
      (node (ref "U$3") (pin "1") (pinfunction "1_1") (pintype "bidirectional"))
    )
    (net (code "103") (name "Net-(OK3B-A)") (class "Default")
      (node (ref "OK3") (pin "3") (pinfunction "A_3") (pintype "passive"))
      (node (ref "R10") (pin "2") (pinfunction "2_2") (pintype "passive"))
    )
    (net (code "104") (name "Net-(OK3B-EMIT)") (class "Default")
      (node (ref "OK3") (pin "13") (pinfunction "EMIT_13") (pintype "passive"))
      (node (ref "U$3") (pin "2") (pinfunction "2_2") (pintype "bidirectional"))
    )
    (net (code "105") (name "Net-(OK3C-A)") (class "Default")
      (node (ref "OK3") (pin "5") (pinfunction "A_5") (pintype "passive"))
      (node (ref "R11") (pin "2") (pinfunction "2_2") (pintype "passive"))
    )
    (net (code "106") (name "Net-(OK3C-EMIT)") (class "Default")
      (node (ref "OK3") (pin "11") (pinfunction "EMIT_11") (pintype "passive"))
      (node (ref "U$3") (pin "3") (pinfunction "3_3") (pintype "bidirectional"))
    )
    (net (code "107") (name "Net-(OK3D-A)") (class "Default")
      (node (ref "OK3") (pin "7") (pinfunction "A_7") (pintype "passive"))
      (node (ref "R12") (pin "2") (pinfunction "2_2") (pintype "passive"))
    )
    (net (code "108") (name "Net-(OK3D-EMIT)") (class "Default")
      (node (ref "OK3") (pin "9") (pinfunction "EMIT_9") (pintype "passive"))
      (node (ref "U$3") (pin "4") (pinfunction "4_4") (pintype "bidirectional"))
    )
    (net (code "109") (name "Net-(OK4A-A)") (class "Default")
      (node (ref "OK4") (pin "1") (pinfunction "A_1") (pintype "passive"))
      (node (ref "R13") (pin "2") (pinfunction "2_2") (pintype "passive"))
    )
    (net (code "110") (name "Net-(OK4A-EMIT)") (class "Default")
      (node (ref "OK4") (pin "15") (pinfunction "EMIT_15") (pintype "passive"))
      (node (ref "U$4") (pin "1") (pinfunction "1_1") (pintype "bidirectional"))
    )
    (net (code "111") (name "Net-(OK4B-A)") (class "Default")
      (node (ref "OK4") (pin "3") (pinfunction "A_3") (pintype "passive"))
      (node (ref "R14") (pin "2") (pinfunction "2_2") (pintype "passive"))
    )
    (net (code "112") (name "Net-(OK4B-EMIT)") (class "Default")
      (node (ref "OK4") (pin "13") (pinfunction "EMIT_13") (pintype "passive"))
      (node (ref "U$4") (pin "2") (pinfunction "2_2") (pintype "bidirectional"))
    )
    (net (code "113") (name "Net-(OK4C-A)") (class "Default")
      (node (ref "OK4") (pin "5") (pinfunction "A_5") (pintype "passive"))
      (node (ref "R15") (pin "2") (pinfunction "2_2") (pintype "passive"))
    )
    (net (code "114") (name "Net-(OK4C-EMIT)") (class "Default")
      (node (ref "OK4") (pin "11") (pinfunction "EMIT_11") (pintype "passive"))
      (node (ref "U$4") (pin "3") (pinfunction "3_3") (pintype "bidirectional"))
    )
    (net (code "115") (name "Net-(OK4D-A)") (class "Default")
      (node (ref "OK4") (pin "7") (pinfunction "A_7") (pintype "passive"))
      (node (ref "R16") (pin "2") (pinfunction "2_2") (pintype "passive"))
    )
    (net (code "116") (name "Net-(OK4D-EMIT)") (class "Default")
      (node (ref "OK4") (pin "9") (pinfunction "EMIT_9") (pintype "passive"))
      (node (ref "U$4") (pin "4") (pinfunction "4_4") (pintype "bidirectional"))
    )
    (net (code "117") (name "Net-(OK5A-A)") (class "Default")
      (node (ref "OK5") (pin "1") (pinfunction "A_1") (pintype "passive"))
      (node (ref "R17") (pin "2") (pinfunction "2_2") (pintype "passive"))
    )
    (net (code "118") (name "Net-(OK5A-EMIT)") (class "Default")
      (node (ref "OK5") (pin "15") (pinfunction "EMIT_15") (pintype "passive"))
      (node (ref "U$5") (pin "1") (pinfunction "1_1") (pintype "bidirectional"))
    )
    (net (code "119") (name "Net-(OK5B-A)") (class "Default")
      (node (ref "OK5") (pin "3") (pinfunction "A_3") (pintype "passive"))
      (node (ref "R18") (pin "2") (pinfunction "2_2") (pintype "passive"))
    )
    (net (code "120") (name "Net-(OK5B-EMIT)") (class "Default")
      (node (ref "OK5") (pin "13") (pinfunction "EMIT_13") (pintype "passive"))
      (node (ref "U$5") (pin "2") (pinfunction "2_2") (pintype "bidirectional"))
    )
    (net (code "121") (name "Net-(OK5C-A)") (class "Default")
      (node (ref "OK5") (pin "5") (pinfunction "A_5") (pintype "passive"))
      (node (ref "R19") (pin "2") (pinfunction "2_2") (pintype "passive"))
    )
    (net (code "122") (name "Net-(OK5C-EMIT)") (class "Default")
      (node (ref "OK5") (pin "11") (pinfunction "EMIT_11") (pintype "passive"))
      (node (ref "U$5") (pin "3") (pinfunction "3_3") (pintype "bidirectional"))
    )
    (net (code "123") (name "Net-(OK5D-A)") (class "Default")
      (node (ref "OK5") (pin "7") (pinfunction "A_7") (pintype "passive"))
      (node (ref "R20") (pin "2") (pinfunction "2_2") (pintype "passive"))
    )
    (net (code "124") (name "Net-(OK5D-EMIT)") (class "Default")
      (node (ref "OK5") (pin "9") (pinfunction "EMIT_9") (pintype "passive"))
      (node (ref "U$5") (pin "4") (pinfunction "4_4") (pintype "bidirectional"))
    )
    (net (code "125") (name "Net-(OK6A-A)") (class "Default")
      (node (ref "OK6") (pin "1") (pinfunction "A_1") (pintype "passive"))
      (node (ref "R21") (pin "2") (pinfunction "2_2") (pintype "passive"))
    )
    (net (code "126") (name "Net-(OK6A-EMIT)") (class "Default")
      (node (ref "OK6") (pin "15") (pinfunction "EMIT_15") (pintype "passive"))
      (node (ref "U$6") (pin "1") (pinfunction "1_1") (pintype "bidirectional"))
    )
    (net (code "127") (name "Net-(OK6B-A)") (class "Default")
      (node (ref "OK6") (pin "3") (pinfunction "A_3") (pintype "passive"))
      (node (ref "R22") (pin "2") (pinfunction "2_2") (pintype "passive"))
    )
    (net (code "128") (name "Net-(OK6B-EMIT)") (class "Default")
      (node (ref "OK6") (pin "13") (pinfunction "EMIT_13") (pintype "passive"))
      (node (ref "U$6") (pin "2") (pinfunction "2_2") (pintype "bidirectional"))
    )
    (net (code "129") (name "Net-(OK6C-A)") (class "Default")
      (node (ref "OK6") (pin "5") (pinfunction "A_5") (pintype "passive"))
      (node (ref "R23") (pin "2") (pinfunction "2_2") (pintype "passive"))
    )
    (net (code "130") (name "Net-(OK6C-EMIT)") (class "Default")
      (node (ref "OK6") (pin "11") (pinfunction "EMIT_11") (pintype "passive"))
      (node (ref "U$6") (pin "3") (pinfunction "3_3") (pintype "bidirectional"))
    )
    (net (code "131") (name "Net-(OK6D-A)") (class "Default")
      (node (ref "OK6") (pin "7") (pinfunction "A_7") (pintype "passive"))
      (node (ref "R24") (pin "2") (pinfunction "2_2") (pintype "passive"))
    )
    (net (code "132") (name "Net-(OK6D-EMIT)") (class "Default")
      (node (ref "OK6") (pin "9") (pinfunction "EMIT_9") (pintype "passive"))
      (node (ref "U$6") (pin "4") (pinfunction "4_4") (pintype "bidirectional"))
    )
    (net (code "133") (name "Net-(OK7A-A)") (class "Default")
      (node (ref "OK7") (pin "1") (pinfunction "A_1") (pintype "passive"))
      (node (ref "R25") (pin "2") (pinfunction "2_2") (pintype "passive"))
    )
    (net (code "134") (name "Net-(OK7A-EMIT)") (class "Default")
      (node (ref "OK7") (pin "15") (pinfunction "EMIT_15") (pintype "passive"))
      (node (ref "U$7") (pin "1") (pinfunction "1_1") (pintype "bidirectional"))
    )
    (net (code "135") (name "Net-(OK7B-A)") (class "Default")
      (node (ref "OK7") (pin "3") (pinfunction "A_3") (pintype "passive"))
      (node (ref "R26") (pin "2") (pinfunction "2_2") (pintype "passive"))
    )
    (net (code "136") (name "Net-(OK7B-EMIT)") (class "Default")
      (node (ref "OK7") (pin "13") (pinfunction "EMIT_13") (pintype "passive"))
      (node (ref "U$7") (pin "2") (pinfunction "2_2") (pintype "bidirectional"))
    )
    (net (code "137") (name "Net-(OK7C-A)") (class "Default")
      (node (ref "OK7") (pin "5") (pinfunction "A_5") (pintype "passive"))
      (node (ref "R27") (pin "2") (pinfunction "2_2") (pintype "passive"))
    )
    (net (code "138") (name "Net-(OK7C-EMIT)") (class "Default")
      (node (ref "OK7") (pin "11") (pinfunction "EMIT_11") (pintype "passive"))
      (node (ref "U$7") (pin "3") (pinfunction "3_3") (pintype "bidirectional"))
    )
    (net (code "139") (name "Net-(OK7D-A)") (class "Default")
      (node (ref "OK7") (pin "7") (pinfunction "A_7") (pintype "passive"))
      (node (ref "R28") (pin "2") (pinfunction "2_2") (pintype "passive"))
    )
    (net (code "140") (name "Net-(OK7D-EMIT)") (class "Default")
      (node (ref "OK7") (pin "9") (pinfunction "EMIT_9") (pintype "passive"))
      (node (ref "U$7") (pin "4") (pinfunction "4_4") (pintype "bidirectional"))
    )
    (net (code "141") (name "Net-(OK8A-A)") (class "Default")
      (node (ref "OK8") (pin "1") (pinfunction "A_1") (pintype "passive"))
      (node (ref "R29") (pin "2") (pinfunction "2_2") (pintype "passive"))
    )
    (net (code "142") (name "Net-(OK8A-EMIT)") (class "Default")
      (node (ref "OK8") (pin "15") (pinfunction "EMIT_15") (pintype "passive"))
      (node (ref "U$8") (pin "1") (pinfunction "1_1") (pintype "bidirectional"))
    )
    (net (code "143") (name "Net-(OK8B-A)") (class "Default")
      (node (ref "OK8") (pin "3") (pinfunction "A_3") (pintype "passive"))
      (node (ref "R30") (pin "2") (pinfunction "2_2") (pintype "passive"))
    )
    (net (code "144") (name "Net-(OK8B-EMIT)") (class "Default")
      (node (ref "OK8") (pin "13") (pinfunction "EMIT_13") (pintype "passive"))
      (node (ref "U$8") (pin "2") (pinfunction "2_2") (pintype "bidirectional"))
    )
    (net (code "145") (name "Net-(OK8C-A)") (class "Default")
      (node (ref "OK8") (pin "5") (pinfunction "A_5") (pintype "passive"))
      (node (ref "R31") (pin "2") (pinfunction "2_2") (pintype "passive"))
    )
    (net (code "146") (name "Net-(OK8C-EMIT)") (class "Default")
      (node (ref "OK8") (pin "11") (pinfunction "EMIT_11") (pintype "passive"))
      (node (ref "U$8") (pin "3") (pinfunction "3_3") (pintype "bidirectional"))
    )
    (net (code "147") (name "Net-(OK8D-A)") (class "Default")
      (node (ref "OK8") (pin "7") (pinfunction "A_7") (pintype "passive"))
      (node (ref "R32") (pin "2") (pinfunction "2_2") (pintype "passive"))
    )
    (net (code "148") (name "Net-(OK8D-EMIT)") (class "Default")
      (node (ref "OK8") (pin "9") (pinfunction "EMIT_9") (pintype "passive"))
      (node (ref "U$8") (pin "4") (pinfunction "4_4") (pintype "bidirectional"))
    )
    (net (code "149") (name "VCC") (class "Default")
      (node (ref "IC1") (pin "10") (pinfunction "SCL_10") (pintype "input"))
      (node (ref "IC2") (pin "10") (pinfunction "SCL_10") (pintype "input"))
      (node (ref "IC3") (pin "10") (pinfunction "SCL_10") (pintype "input"))
      (node (ref "IC4") (pin "10") (pinfunction "SCL_10") (pintype "input"))
      (node (ref "OK1") (pin "10") (pinfunction "COL_10") (pintype "passive"))
      (node (ref "OK1") (pin "12") (pinfunction "COL_12") (pintype "passive"))
      (node (ref "OK1") (pin "14") (pinfunction "COL_14") (pintype "passive"))
      (node (ref "OK1") (pin "16") (pinfunction "COL_16") (pintype "passive"))
      (node (ref "OK2") (pin "10") (pinfunction "COL_10") (pintype "passive"))
      (node (ref "OK2") (pin "12") (pinfunction "COL_12") (pintype "passive"))
      (node (ref "OK2") (pin "14") (pinfunction "COL_14") (pintype "passive"))
      (node (ref "OK2") (pin "16") (pinfunction "COL_16") (pintype "passive"))
      (node (ref "OK3") (pin "10") (pinfunction "COL_10") (pintype "passive"))
      (node (ref "OK3") (pin "12") (pinfunction "COL_12") (pintype "passive"))
      (node (ref "OK3") (pin "14") (pinfunction "COL_14") (pintype "passive"))
      (node (ref "OK3") (pin "16") (pinfunction "COL_16") (pintype "passive"))
      (node (ref "OK4") (pin "10") (pinfunction "COL_10") (pintype "passive"))
      (node (ref "OK4") (pin "12") (pinfunction "COL_12") (pintype "passive"))
      (node (ref "OK4") (pin "14") (pinfunction "COL_14") (pintype "passive"))
      (node (ref "OK4") (pin "16") (pinfunction "COL_16") (pintype "passive"))
      (node (ref "OK5") (pin "10") (pinfunction "COL_10") (pintype "passive"))
      (node (ref "OK5") (pin "12") (pinfunction "COL_12") (pintype "passive"))
      (node (ref "OK5") (pin "14") (pinfunction "COL_14") (pintype "passive"))
      (node (ref "OK5") (pin "16") (pinfunction "COL_16") (pintype "passive"))
      (node (ref "OK6") (pin "10") (pinfunction "COL_10") (pintype "passive"))
      (node (ref "OK6") (pin "12") (pinfunction "COL_12") (pintype "passive"))
      (node (ref "OK6") (pin "14") (pinfunction "COL_14") (pintype "passive"))
      (node (ref "OK6") (pin "16") (pinfunction "COL_16") (pintype "passive"))
      (node (ref "OK7") (pin "10") (pinfunction "COL_10") (pintype "passive"))
      (node (ref "OK7") (pin "12") (pinfunction "COL_12") (pintype "passive"))
      (node (ref "OK7") (pin "14") (pinfunction "COL_14") (pintype "passive"))
      (node (ref "OK7") (pin "16") (pinfunction "COL_16") (pintype "passive"))
      (node (ref "OK8") (pin "10") (pinfunction "COL_10") (pintype "passive"))
      (node (ref "OK8") (pin "12") (pinfunction "COL_12") (pintype "passive"))
      (node (ref "OK8") (pin "14") (pinfunction "COL_14") (pintype "passive"))
      (node (ref "OK8") (pin "16") (pinfunction "COL_16") (pintype "passive"))
      (node (ref "R65") (pin "2") (pinfunction "2_2") (pintype "passive"))
      (node (ref "R67") (pin "2") (pinfunction "2_2") (pintype "passive"))
      (node (ref "R69") (pin "2") (pinfunction "2_2") (pintype "passive"))
      (node (ref "R72") (pin "2") (pinfunction "2_2") (pintype "passive"))
      (node (ref "R74") (pin "2") (pinfunction "2_2") (pintype "passive"))
      (node (ref "R76") (pin "2") (pinfunction "2_2") (pintype "passive"))
      (node (ref "U$100") (pin "JP2.8") (pinfunction "5V_JP2.8") (pintype "power_in"))
    )
    (net (code "150") (name "unconnected-(IC4A-QH*-Pad9)") (class "Default")
      (node (ref "IC4") (pin "9") (pinfunction "QH*_9") (pintype "tri_state"))
    )
    (net (code "151") (name "unconnected-(IC5A-SER-Pad10)") (class "Default")
      (node (ref "IC5") (pin "10") (pinfunction "SER_10") (pintype "input"))
    )
    (net (code "152") (name "unconnected-(IC5A-~{QH}-Pad7)") (class "Default")
      (node (ref "IC5") (pin "7") (pinfunction "~{QH}_7") (pintype "output"))
    )
    (net (code "153") (name "unconnected-(IC6A-~{QH}-Pad7)") (class "Default")
      (node (ref "IC6") (pin "7") (pinfunction "~{QH}_7") (pintype "output"))
    )
    (net (code "154") (name "unconnected-(IC7A-~{QH}-Pad7)") (class "Default")
      (node (ref "IC7") (pin "7") (pinfunction "~{QH}_7") (pintype "output"))
    )
    (net (code "155") (name "unconnected-(IC8A-~{QH}-Pad7)") (class "Default")
      (node (ref "IC8") (pin "7") (pinfunction "~{QH}_7") (pintype "output"))
    )
    (net (code "156") (name "unconnected-(U$100-A0-PadJP1.2)") (class "Default")
      (node (ref "U$100") (pin "JP1.2") (pinfunction "A0_JP1.2") (pintype "bidirectional"))
    )
    (net (code "157") (name "unconnected-(U$100-D0-PadJP1.3)") (class "Default")
      (node (ref "U$100") (pin "JP1.3") (pinfunction "D0_JP1.3") (pintype "bidirectional"))
    )
    (net (code "158") (name "unconnected-(U$100-D4-PadJP2.6)") (class "Default")
      (node (ref "U$100") (pin "JP2.6") (pinfunction "D4_JP2.6") (pintype "bidirectional"))
    )
    (net (code "159") (name "unconnected-(U$100-D8-PadJP1.7)") (class "Default")
      (node (ref "U$100") (pin "JP1.7") (pinfunction "D8_JP1.7") (pintype "bidirectional"))
    )
    (net (code "160") (name "unconnected-(U$100-RST-PadJP1.1)") (class "Default")
      (node (ref "U$100") (pin "JP1.1") (pinfunction "RST_JP1.1") (pintype "bidirectional"))
    )
    (net (code "161") (name "unconnected-(U$100-RX-PadJP2.2)") (class "Default")
      (node (ref "U$100") (pin "JP2.2") (pinfunction "RX_JP2.2") (pintype "bidirectional"))
    )
    (net (code "162") (name "unconnected-(U$100-TX-PadJP2.1)") (class "Default")
      (node (ref "U$100") (pin "JP2.1") (pinfunction "TX_JP2.1") (pintype "bidirectional"))
    )
  )
)
